# SpaceVNXDaughterBoard.net
KiCad netlist of a schematic drawn in Altium Designer
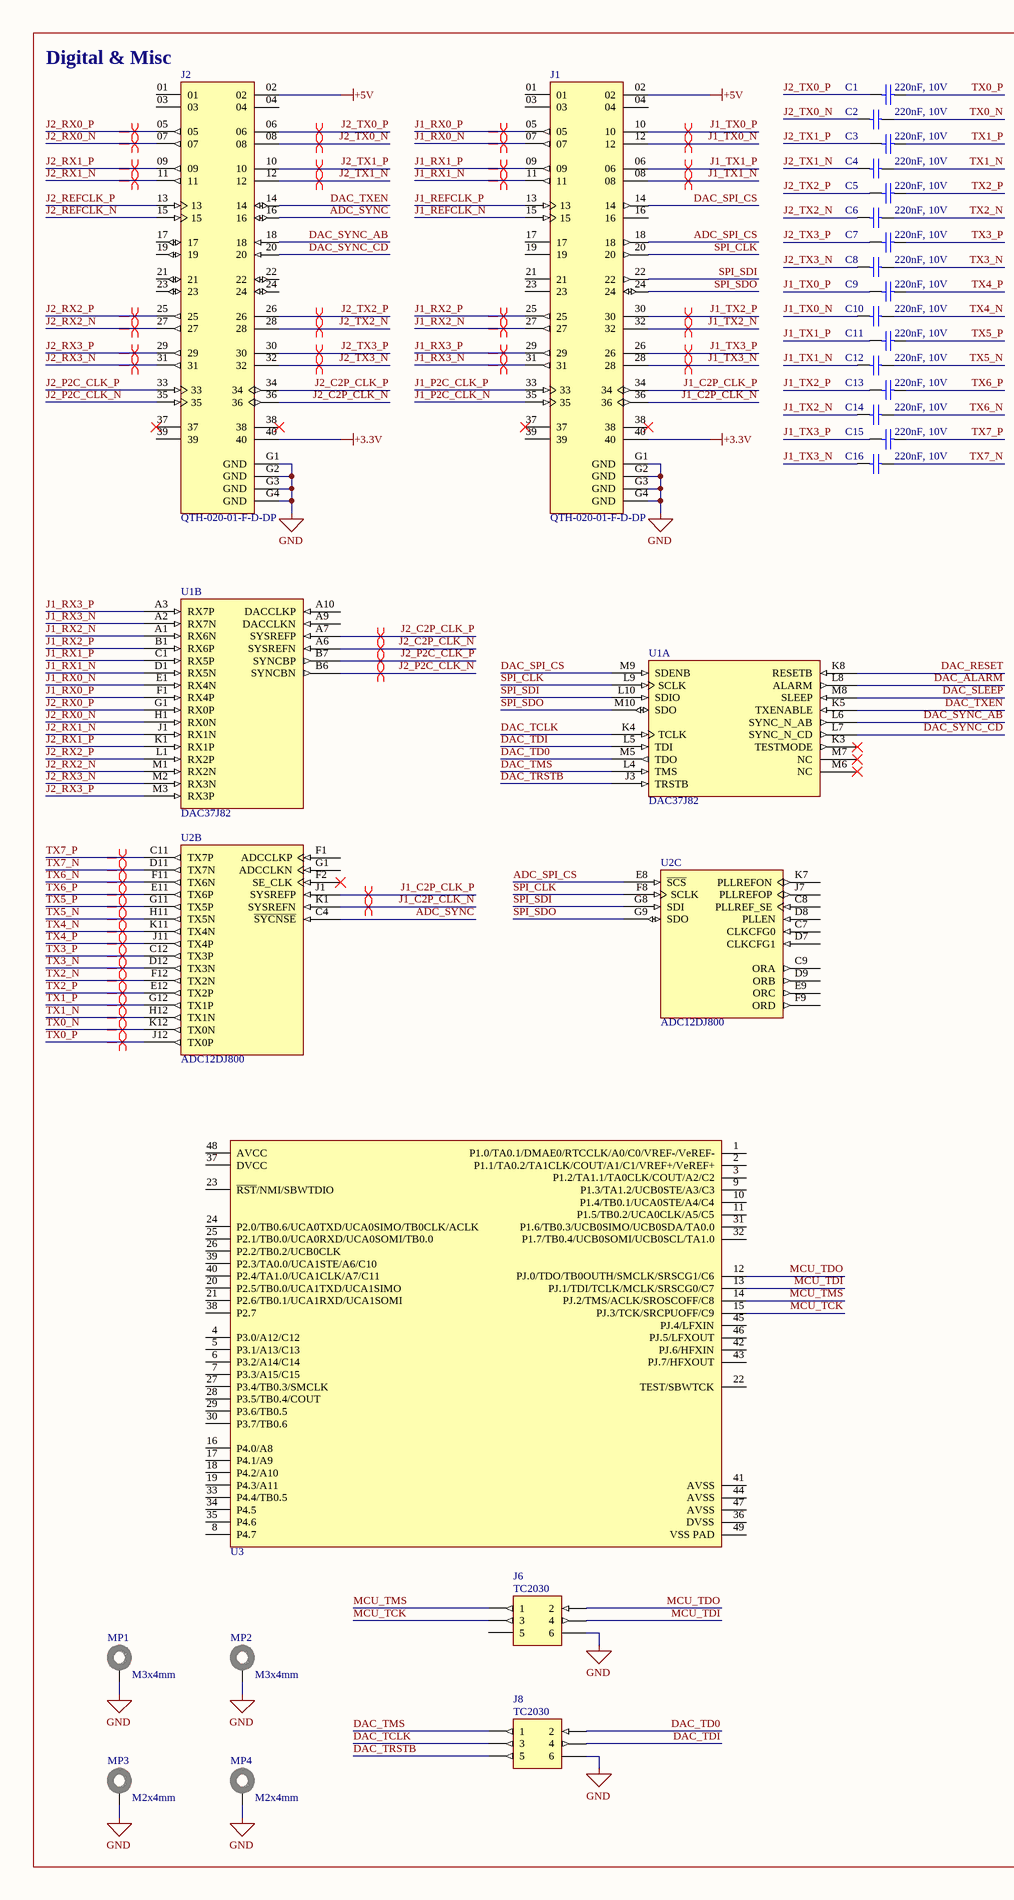
[diagram p0: SpaceVNXDaughterBoard.SchDoc, left]
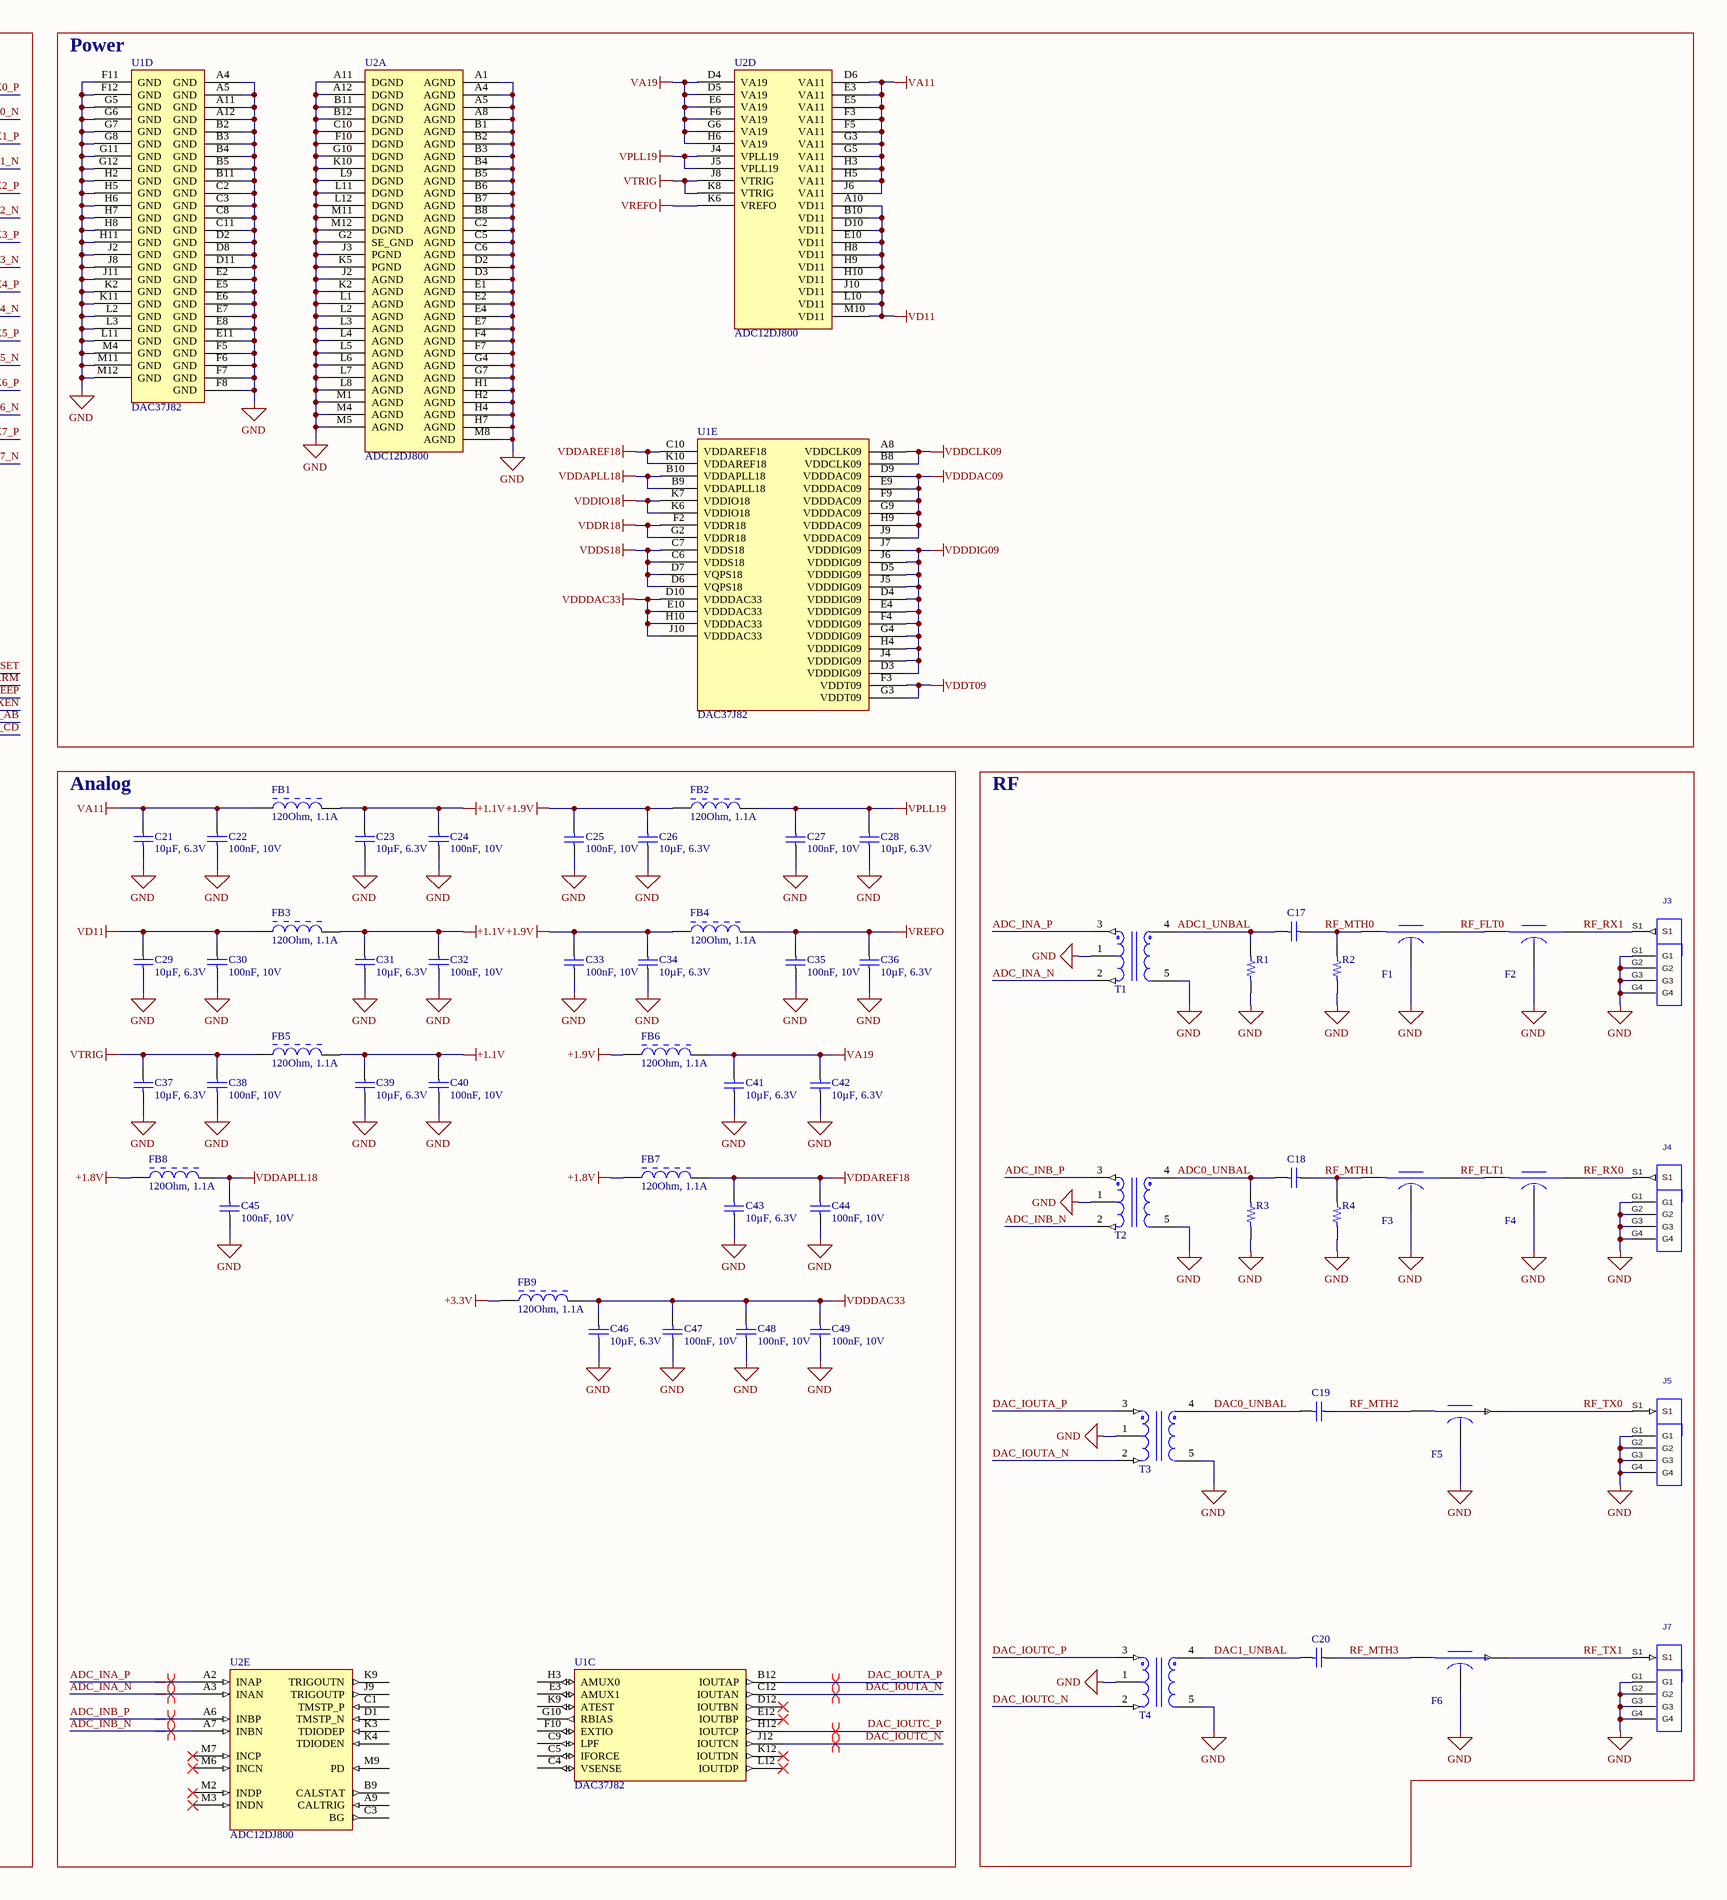
[diagram p1: SpaceVNXDaughterBoard.SchDoc, right]

(export (version "E")
  (design (tool "Eeschema 10.0.6"))
  (components
    (comp (ref "C1")
      (value "220nF, 10V")
      (footprint "WURTH_WCAP-CSGP_0402")
      (description "WCAP-CSGP Multilayer Ceramic Chip Capacitor, General Purpose, size 0402, X5R, 220nF, 10V")
      (fields
        (field (name "MANUFACTURER PART NUMBER") "885012105011")
        (field (name "MANUFACTURER") "Wurth Elektronik")
      )
      (libsource (lib "SpaceVNX") (part "885012105011"))
    )
    (comp (ref "C2")
      (value "220nF, 10V")
      (footprint "WURTH_WCAP-CSGP_0402")
      (description "WCAP-CSGP Multilayer Ceramic Chip Capacitor, General Purpose, size 0402, X5R, 220nF, 10V")
      (fields
        (field (name "MANUFACTURER PART NUMBER") "885012105011")
        (field (name "MANUFACTURER") "Wurth Elektronik")
      )
      (libsource (lib "SpaceVNX") (part "885012105011"))
    )
    (comp (ref "C3")
      (value "220nF, 10V")
      (footprint "WURTH_WCAP-CSGP_0402")
      (description "WCAP-CSGP Multilayer Ceramic Chip Capacitor, General Purpose, size 0402, X5R, 220nF, 10V")
      (fields
        (field (name "MANUFACTURER PART NUMBER") "885012105011")
        (field (name "MANUFACTURER") "Wurth Elektronik")
      )
      (libsource (lib "SpaceVNX") (part "885012105011"))
    )
    (comp (ref "C4")
      (value "220nF, 10V")
      (footprint "WURTH_WCAP-CSGP_0402")
      (description "WCAP-CSGP Multilayer Ceramic Chip Capacitor, General Purpose, size 0402, X5R, 220nF, 10V")
      (fields
        (field (name "MANUFACTURER PART NUMBER") "885012105011")
        (field (name "MANUFACTURER") "Wurth Elektronik")
      )
      (libsource (lib "SpaceVNX") (part "885012105011"))
    )
    (comp (ref "C5")
      (value "220nF, 10V")
      (footprint "WURTH_WCAP-CSGP_0402")
      (description "WCAP-CSGP Multilayer Ceramic Chip Capacitor, General Purpose, size 0402, X5R, 220nF, 10V")
      (fields
        (field (name "MANUFACTURER PART NUMBER") "885012105011")
        (field (name "MANUFACTURER") "Wurth Elektronik")
      )
      (libsource (lib "SpaceVNX") (part "885012105011"))
    )
    (comp (ref "C6")
      (value "220nF, 10V")
      (footprint "WURTH_WCAP-CSGP_0402")
      (description "WCAP-CSGP Multilayer Ceramic Chip Capacitor, General Purpose, size 0402, X5R, 220nF, 10V")
      (fields
        (field (name "MANUFACTURER PART NUMBER") "885012105011")
        (field (name "MANUFACTURER") "Wurth Elektronik")
      )
      (libsource (lib "SpaceVNX") (part "885012105011"))
    )
    (comp (ref "C7")
      (value "220nF, 10V")
      (footprint "WURTH_WCAP-CSGP_0402")
      (description "WCAP-CSGP Multilayer Ceramic Chip Capacitor, General Purpose, size 0402, X5R, 220nF, 10V")
      (fields
        (field (name "MANUFACTURER PART NUMBER") "885012105011")
        (field (name "MANUFACTURER") "Wurth Elektronik")
      )
      (libsource (lib "SpaceVNX") (part "885012105011"))
    )
    (comp (ref "C8")
      (value "220nF, 10V")
      (footprint "WURTH_WCAP-CSGP_0402")
      (description "WCAP-CSGP Multilayer Ceramic Chip Capacitor, General Purpose, size 0402, X5R, 220nF, 10V")
      (fields
        (field (name "MANUFACTURER PART NUMBER") "885012105011")
        (field (name "MANUFACTURER") "Wurth Elektronik")
      )
      (libsource (lib "SpaceVNX") (part "885012105011"))
    )
    (comp (ref "C9")
      (value "220nF, 10V")
      (footprint "WURTH_WCAP-CSGP_0402")
      (description "WCAP-CSGP Multilayer Ceramic Chip Capacitor, General Purpose, size 0402, X5R, 220nF, 10V")
      (fields
        (field (name "MANUFACTURER PART NUMBER") "885012105011")
        (field (name "MANUFACTURER") "Wurth Elektronik")
      )
      (libsource (lib "SpaceVNX") (part "885012105011"))
    )
    (comp (ref "C10")
      (value "220nF, 10V")
      (footprint "WURTH_WCAP-CSGP_0402")
      (description "WCAP-CSGP Multilayer Ceramic Chip Capacitor, General Purpose, size 0402, X5R, 220nF, 10V")
      (fields
        (field (name "MANUFACTURER PART NUMBER") "885012105011")
        (field (name "MANUFACTURER") "Wurth Elektronik")
      )
      (libsource (lib "SpaceVNX") (part "885012105011"))
    )
    (comp (ref "C11")
      (value "220nF, 10V")
      (footprint "WURTH_WCAP-CSGP_0402")
      (description "WCAP-CSGP Multilayer Ceramic Chip Capacitor, General Purpose, size 0402, X5R, 220nF, 10V")
      (fields
        (field (name "MANUFACTURER PART NUMBER") "885012105011")
        (field (name "MANUFACTURER") "Wurth Elektronik")
      )
      (libsource (lib "SpaceVNX") (part "885012105011"))
    )
    (comp (ref "C12")
      (value "220nF, 10V")
      (footprint "WURTH_WCAP-CSGP_0402")
      (description "WCAP-CSGP Multilayer Ceramic Chip Capacitor, General Purpose, size 0402, X5R, 220nF, 10V")
      (fields
        (field (name "MANUFACTURER PART NUMBER") "885012105011")
        (field (name "MANUFACTURER") "Wurth Elektronik")
      )
      (libsource (lib "SpaceVNX") (part "885012105011"))
    )
    (comp (ref "C13")
      (value "220nF, 10V")
      (footprint "WURTH_WCAP-CSGP_0402")
      (description "WCAP-CSGP Multilayer Ceramic Chip Capacitor, General Purpose, size 0402, X5R, 220nF, 10V")
      (fields
        (field (name "MANUFACTURER PART NUMBER") "885012105011")
        (field (name "MANUFACTURER") "Wurth Elektronik")
      )
      (libsource (lib "SpaceVNX") (part "885012105011"))
    )
    (comp (ref "C14")
      (value "220nF, 10V")
      (footprint "WURTH_WCAP-CSGP_0402")
      (description "WCAP-CSGP Multilayer Ceramic Chip Capacitor, General Purpose, size 0402, X5R, 220nF, 10V")
      (fields
        (field (name "MANUFACTURER PART NUMBER") "885012105011")
        (field (name "MANUFACTURER") "Wurth Elektronik")
      )
      (libsource (lib "SpaceVNX") (part "885012105011"))
    )
    (comp (ref "C15")
      (value "220nF, 10V")
      (footprint "WURTH_WCAP-CSGP_0402")
      (description "WCAP-CSGP Multilayer Ceramic Chip Capacitor, General Purpose, size 0402, X5R, 220nF, 10V")
      (fields
        (field (name "MANUFACTURER PART NUMBER") "885012105011")
        (field (name "MANUFACTURER") "Wurth Elektronik")
      )
      (libsource (lib "SpaceVNX") (part "885012105011"))
    )
    (comp (ref "C16")
      (value "220nF, 10V")
      (footprint "WURTH_WCAP-CSGP_0402")
      (description "WCAP-CSGP Multilayer Ceramic Chip Capacitor, General Purpose, size 0402, X5R, 220nF, 10V")
      (fields
        (field (name "MANUFACTURER PART NUMBER") "885012105011")
        (field (name "MANUFACTURER") "Wurth Elektronik")
      )
      (libsource (lib "SpaceVNX") (part "885012105011"))
    )
    (comp (ref "C17")
      (value "10pF, 16V")
      (footprint "WURTH_WCAP-CSGP_0402")
      (description "WCAP-CSGP Multilayer Ceramic Chip Capacitor, General Purpose, size 0402, NP0, 10pF, 16V")
      (fields
        (field (name "MANUFACTURER PART NUMBER") "885012005025")
        (field (name "MANUFACTURER") "Wurth Elektronik")
      )
      (libsource (lib "SpaceVNX") (part "885012005025"))
    )
    (comp (ref "C18")
      (value "10pF, 16V")
      (footprint "WURTH_WCAP-CSGP_0402")
      (description "WCAP-CSGP Multilayer Ceramic Chip Capacitor, General Purpose, size 0402, NP0, 10pF, 16V")
      (fields
        (field (name "MANUFACTURER PART NUMBER") "885012005025")
        (field (name "MANUFACTURER") "Wurth Elektronik")
      )
      (libsource (lib "SpaceVNX") (part "885012005025"))
    )
    (comp (ref "C19")
      (value "10pF, 16V")
      (footprint "WURTH_WCAP-CSGP_0402")
      (description "WCAP-CSGP Multilayer Ceramic Chip Capacitor, General Purpose, size 0402, NP0, 10pF, 16V")
      (fields
        (field (name "MANUFACTURER PART NUMBER") "885012005025")
        (field (name "MANUFACTURER") "Wurth Elektronik")
      )
      (libsource (lib "SpaceVNX") (part "885012005025"))
    )
    (comp (ref "C20")
      (value "10pF, 16V")
      (footprint "WURTH_WCAP-CSGP_0402")
      (description "WCAP-CSGP Multilayer Ceramic Chip Capacitor, General Purpose, size 0402, NP0, 10pF, 16V")
      (fields
        (field (name "MANUFACTURER PART NUMBER") "885012005025")
        (field (name "MANUFACTURER") "Wurth Elektronik")
      )
      (libsource (lib "SpaceVNX") (part "885012005025"))
    )
    (comp (ref "C21")
      (value "10µF, 6.3V")
      (footprint "WURTH_WCAP-CSGP_0402")
      (description "WCAP-CSGP Multilayer Ceramic Chip Capacitor, General Purpose, size 0402, X5R, 10uF, 6.3V")
      (fields
        (field (name "MANUFACTURER PART NUMBER") "885012105020")
        (field (name "MANUFACTURER") "Wurth Elektronik")
      )
      (libsource (lib "SpaceVNX") (part "885012105020"))
    )
    (comp (ref "C22")
      (value "100nF, 10V")
      (footprint "WURTH_WCAP-CSGP_0402")
      (description "WCAP-CSGP Multilayer Ceramic Chip Capacitor, General Purpose, size 0402, X7R, 100nF, 10V")
      (fields
        (field (name "MANUFACTURER PART NUMBER") "885012205018")
        (field (name "MANUFACTURER") "Wurth Elektronik")
      )
      (libsource (lib "SpaceVNX") (part "885012205018"))
    )
    (comp (ref "C23")
      (value "10µF, 6.3V")
      (footprint "WURTH_WCAP-CSGP_0402")
      (description "WCAP-CSGP Multilayer Ceramic Chip Capacitor, General Purpose, size 0402, X5R, 10uF, 6.3V")
      (fields
        (field (name "MANUFACTURER PART NUMBER") "885012105020")
        (field (name "MANUFACTURER") "Wurth Elektronik")
      )
      (libsource (lib "SpaceVNX") (part "885012105020"))
    )
    (comp (ref "C24")
      (value "100nF, 10V")
      (footprint "WURTH_WCAP-CSGP_0402")
      (description "WCAP-CSGP Multilayer Ceramic Chip Capacitor, General Purpose, size 0402, X7R, 100nF, 10V")
      (fields
        (field (name "MANUFACTURER PART NUMBER") "885012205018")
        (field (name "MANUFACTURER") "Wurth Elektronik")
      )
      (libsource (lib "SpaceVNX") (part "885012205018"))
    )
    (comp (ref "C25")
      (value "100nF, 10V")
      (footprint "WURTH_WCAP-CSGP_0402")
      (description "WCAP-CSGP Multilayer Ceramic Chip Capacitor, General Purpose, size 0402, X7R, 100nF, 10V")
      (fields
        (field (name "MANUFACTURER PART NUMBER") "885012205018")
        (field (name "MANUFACTURER") "Wurth Elektronik")
      )
      (libsource (lib "SpaceVNX") (part "885012205018"))
    )
    (comp (ref "C26")
      (value "10µF, 6.3V")
      (footprint "WURTH_WCAP-CSGP_0402")
      (description "WCAP-CSGP Multilayer Ceramic Chip Capacitor, General Purpose, size 0402, X5R, 10uF, 6.3V")
      (fields
        (field (name "MANUFACTURER PART NUMBER") "885012105020")
        (field (name "MANUFACTURER") "Wurth Elektronik")
      )
      (libsource (lib "SpaceVNX") (part "885012105020"))
    )
    (comp (ref "C27")
      (value "100nF, 10V")
      (footprint "WURTH_WCAP-CSGP_0402")
      (description "WCAP-CSGP Multilayer Ceramic Chip Capacitor, General Purpose, size 0402, X7R, 100nF, 10V")
      (fields
        (field (name "MANUFACTURER PART NUMBER") "885012205018")
        (field (name "MANUFACTURER") "Wurth Elektronik")
      )
      (libsource (lib "SpaceVNX") (part "885012205018"))
    )
    (comp (ref "C28")
      (value "10µF, 6.3V")
      (footprint "WURTH_WCAP-CSGP_0402")
      (description "WCAP-CSGP Multilayer Ceramic Chip Capacitor, General Purpose, size 0402, X5R, 10uF, 6.3V")
      (fields
        (field (name "MANUFACTURER PART NUMBER") "885012105020")
        (field (name "MANUFACTURER") "Wurth Elektronik")
      )
      (libsource (lib "SpaceVNX") (part "885012105020"))
    )
    (comp (ref "C29")
      (value "10µF, 6.3V")
      (footprint "WURTH_WCAP-CSGP_0402")
      (description "WCAP-CSGP Multilayer Ceramic Chip Capacitor, General Purpose, size 0402, X5R, 10uF, 6.3V")
      (fields
        (field (name "MANUFACTURER PART NUMBER") "885012105020")
        (field (name "MANUFACTURER") "Wurth Elektronik")
      )
      (libsource (lib "SpaceVNX") (part "885012105020"))
    )
    (comp (ref "C30")
      (value "100nF, 10V")
      (footprint "WURTH_WCAP-CSGP_0402")
      (description "WCAP-CSGP Multilayer Ceramic Chip Capacitor, General Purpose, size 0402, X7R, 100nF, 10V")
      (fields
        (field (name "MANUFACTURER PART NUMBER") "885012205018")
        (field (name "MANUFACTURER") "Wurth Elektronik")
      )
      (libsource (lib "SpaceVNX") (part "885012205018"))
    )
    (comp (ref "C31")
      (value "10µF, 6.3V")
      (footprint "WURTH_WCAP-CSGP_0402")
      (description "WCAP-CSGP Multilayer Ceramic Chip Capacitor, General Purpose, size 0402, X5R, 10uF, 6.3V")
      (fields
        (field (name "MANUFACTURER PART NUMBER") "885012105020")
        (field (name "MANUFACTURER") "Wurth Elektronik")
      )
      (libsource (lib "SpaceVNX") (part "885012105020"))
    )
    (comp (ref "C32")
      (value "100nF, 10V")
      (footprint "WURTH_WCAP-CSGP_0402")
      (description "WCAP-CSGP Multilayer Ceramic Chip Capacitor, General Purpose, size 0402, X7R, 100nF, 10V")
      (fields
        (field (name "MANUFACTURER PART NUMBER") "885012205018")
        (field (name "MANUFACTURER") "Wurth Elektronik")
      )
      (libsource (lib "SpaceVNX") (part "885012205018"))
    )
    (comp (ref "C33")
      (value "100nF, 10V")
      (footprint "WURTH_WCAP-CSGP_0402")
      (description "WCAP-CSGP Multilayer Ceramic Chip Capacitor, General Purpose, size 0402, X7R, 100nF, 10V")
      (fields
        (field (name "MANUFACTURER PART NUMBER") "885012205018")
        (field (name "MANUFACTURER") "Wurth Elektronik")
      )
      (libsource (lib "SpaceVNX") (part "885012205018"))
    )
    (comp (ref "C34")
      (value "10µF, 6.3V")
      (footprint "WURTH_WCAP-CSGP_0402")
      (description "WCAP-CSGP Multilayer Ceramic Chip Capacitor, General Purpose, size 0402, X5R, 10uF, 6.3V")
      (fields
        (field (name "MANUFACTURER PART NUMBER") "885012105020")
        (field (name "MANUFACTURER") "Wurth Elektronik")
      )
      (libsource (lib "SpaceVNX") (part "885012105020"))
    )
    (comp (ref "C35")
      (value "100nF, 10V")
      (footprint "WURTH_WCAP-CSGP_0402")
      (description "WCAP-CSGP Multilayer Ceramic Chip Capacitor, General Purpose, size 0402, X7R, 100nF, 10V")
      (fields
        (field (name "MANUFACTURER PART NUMBER") "885012205018")
        (field (name "MANUFACTURER") "Wurth Elektronik")
      )
      (libsource (lib "SpaceVNX") (part "885012205018"))
    )
    (comp (ref "C36")
      (value "10µF, 6.3V")
      (footprint "WURTH_WCAP-CSGP_0402")
      (description "WCAP-CSGP Multilayer Ceramic Chip Capacitor, General Purpose, size 0402, X5R, 10uF, 6.3V")
      (fields
        (field (name "MANUFACTURER PART NUMBER") "885012105020")
        (field (name "MANUFACTURER") "Wurth Elektronik")
      )
      (libsource (lib "SpaceVNX") (part "885012105020"))
    )
    (comp (ref "C37")
      (value "10µF, 6.3V")
      (footprint "WURTH_WCAP-CSGP_0402")
      (description "WCAP-CSGP Multilayer Ceramic Chip Capacitor, General Purpose, size 0402, X5R, 10uF, 6.3V")
      (fields
        (field (name "MANUFACTURER PART NUMBER") "885012105020")
        (field (name "MANUFACTURER") "Wurth Elektronik")
      )
      (libsource (lib "SpaceVNX") (part "885012105020"))
    )
    (comp (ref "C38")
      (value "100nF, 10V")
      (footprint "WURTH_WCAP-CSGP_0402")
      (description "WCAP-CSGP Multilayer Ceramic Chip Capacitor, General Purpose, size 0402, X7R, 100nF, 10V")
      (fields
        (field (name "MANUFACTURER PART NUMBER") "885012205018")
        (field (name "MANUFACTURER") "Wurth Elektronik")
      )
      (libsource (lib "SpaceVNX") (part "885012205018"))
    )
    (comp (ref "C39")
      (value "10µF, 6.3V")
      (footprint "WURTH_WCAP-CSGP_0402")
      (description "WCAP-CSGP Multilayer Ceramic Chip Capacitor, General Purpose, size 0402, X5R, 10uF, 6.3V")
      (fields
        (field (name "MANUFACTURER PART NUMBER") "885012105020")
        (field (name "MANUFACTURER") "Wurth Elektronik")
      )
      (libsource (lib "SpaceVNX") (part "885012105020"))
    )
    (comp (ref "C40")
      (value "100nF, 10V")
      (footprint "WURTH_WCAP-CSGP_0402")
      (description "WCAP-CSGP Multilayer Ceramic Chip Capacitor, General Purpose, size 0402, X7R, 100nF, 10V")
      (fields
        (field (name "MANUFACTURER PART NUMBER") "885012205018")
        (field (name "MANUFACTURER") "Wurth Elektronik")
      )
      (libsource (lib "SpaceVNX") (part "885012205018"))
    )
    (comp (ref "C41")
      (value "10µF, 6.3V")
      (footprint "WURTH_WCAP-CSGP_0402")
      (description "WCAP-CSGP Multilayer Ceramic Chip Capacitor, General Purpose, size 0402, X5R, 10uF, 6.3V")
      (fields
        (field (name "MANUFACTURER PART NUMBER") "885012105020")
        (field (name "MANUFACTURER") "Wurth Elektronik")
      )
      (libsource (lib "SpaceVNX") (part "885012105020"))
    )
    (comp (ref "C42")
      (value "10µF, 6.3V")
      (footprint "WURTH_WCAP-CSGP_0402")
      (description "WCAP-CSGP Multilayer Ceramic Chip Capacitor, General Purpose, size 0402, X5R, 10uF, 6.3V")
      (fields
        (field (name "MANUFACTURER PART NUMBER") "885012105020")
        (field (name "MANUFACTURER") "Wurth Elektronik")
      )
      (libsource (lib "SpaceVNX") (part "885012105020"))
    )
    (comp (ref "C43")
      (value "10µF, 6.3V")
      (footprint "WURTH_WCAP-CSGP_0402")
      (description "WCAP-CSGP Multilayer Ceramic Chip Capacitor, General Purpose, size 0402, X5R, 10uF, 6.3V")
      (fields
        (field (name "MANUFACTURER PART NUMBER") "885012105020")
        (field (name "MANUFACTURER") "Wurth Elektronik")
      )
      (libsource (lib "SpaceVNX") (part "885012105020"))
    )
    (comp (ref "C44")
      (value "100nF, 10V")
      (footprint "WURTH_WCAP-CSGP_0402")
      (description "WCAP-CSGP Multilayer Ceramic Chip Capacitor, General Purpose, size 0402, X7R, 100nF, 10V")
      (fields
        (field (name "MANUFACTURER PART NUMBER") "885012205018")
        (field (name "MANUFACTURER") "Wurth Elektronik")
      )
      (libsource (lib "SpaceVNX") (part "885012205018"))
    )
    (comp (ref "C45")
      (value "100nF, 10V")
      (footprint "WURTH_WCAP-CSGP_0402")
      (description "WCAP-CSGP Multilayer Ceramic Chip Capacitor, General Purpose, size 0402, X7R, 100nF, 10V")
      (fields
        (field (name "MANUFACTURER PART NUMBER") "885012205018")
        (field (name "MANUFACTURER") "Wurth Elektronik")
      )
      (libsource (lib "SpaceVNX") (part "885012205018"))
    )
    (comp (ref "C46")
      (value "10µF, 6.3V")
      (footprint "WURTH_WCAP-CSGP_0402")
      (description "WCAP-CSGP Multilayer Ceramic Chip Capacitor, General Purpose, size 0402, X5R, 10uF, 6.3V")
      (fields
        (field (name "MANUFACTURER PART NUMBER") "885012105020")
        (field (name "MANUFACTURER") "Wurth Elektronik")
      )
      (libsource (lib "SpaceVNX") (part "885012105020"))
    )
    (comp (ref "C47")
      (value "100nF, 10V")
      (footprint "WURTH_WCAP-CSGP_0402")
      (description "WCAP-CSGP Multilayer Ceramic Chip Capacitor, General Purpose, size 0402, X7R, 100nF, 10V")
      (fields
        (field (name "MANUFACTURER PART NUMBER") "885012205018")
        (field (name "MANUFACTURER") "Wurth Elektronik")
      )
      (libsource (lib "SpaceVNX") (part "885012205018"))
    )
    (comp (ref "C48")
      (value "100nF, 10V")
      (footprint "WURTH_WCAP-CSGP_0402")
      (description "WCAP-CSGP Multilayer Ceramic Chip Capacitor, General Purpose, size 0402, X7R, 100nF, 10V")
      (fields
        (field (name "MANUFACTURER PART NUMBER") "885012205018")
        (field (name "MANUFACTURER") "Wurth Elektronik")
      )
      (libsource (lib "SpaceVNX") (part "885012205018"))
    )
    (comp (ref "C49")
      (value "100nF, 10V")
      (footprint "WURTH_WCAP-CSGP_0402")
      (description "WCAP-CSGP Multilayer Ceramic Chip Capacitor, General Purpose, size 0402, X7R, 100nF, 10V")
      (fields
        (field (name "MANUFACTURER PART NUMBER") "885012205018")
        (field (name "MANUFACTURER") "Wurth Elektronik")
      )
      (libsource (lib "SpaceVNX") (part "885012205018"))
    )
    (comp (ref "F1")
      (value "BFTC-XXXX+")
      (footprint "Mini-Circuits_FV1206")
      (description "Band Pass RF Filter")
      (fields (field (name "MANUFACTURER") "Mini-Circuits"))
      (libsource (lib "SpaceVNX") (part "BFTC-XXXX+"))
    )
    (comp (ref "F2")
      (value "BFTC-XXXX+")
      (footprint "Mini-Circuits_FV1206")
      (description "Band Pass RF Filter")
      (fields (field (name "MANUFACTURER") "Mini-Circuits"))
      (libsource (lib "SpaceVNX") (part "BFTC-XXXX+"))
    )
    (comp (ref "F3")
      (value "BFTC-XXXX+")
      (footprint "Mini-Circuits_FV1206")
      (description "Band Pass RF Filter")
      (fields (field (name "MANUFACTURER") "Mini-Circuits"))
      (libsource (lib "SpaceVNX") (part "BFTC-XXXX+"))
    )
    (comp (ref "F4")
      (value "BFTC-XXXX+")
      (footprint "Mini-Circuits_FV1206")
      (description "Band Pass RF Filter")
      (fields (field (name "MANUFACTURER") "Mini-Circuits"))
      (libsource (lib "SpaceVNX") (part "BFTC-XXXX+"))
    )
    (comp (ref "F5")
      (value "BFTC-XXXX+")
      (footprint "Mini-Circuits_FV1206")
      (description "Band Pass RF Filter")
      (fields (field (name "MANUFACTURER") "Mini-Circuits"))
      (libsource (lib "SpaceVNX") (part "BFTC-XXXX+"))
    )
    (comp (ref "F6")
      (value "BFTC-XXXX+")
      (footprint "Mini-Circuits_FV1206")
      (description "Band Pass RF Filter")
      (fields (field (name "MANUFACTURER") "Mini-Circuits"))
      (libsource (lib "SpaceVNX") (part "BFTC-XXXX+"))
    )
    (comp (ref "FB1")
      (value "120Ohm, 1.1A")
      (footprint "WURTH-CBF_0402")
      (description "WE-CBF SMT EMI Suppression Ferrite Bead, size 0402, 120Ohm, 1.1A")
      (fields
        (field (name "MANUFACTURER PART NUMBER") "74279271")
        (field (name "MANUFACTURER") "Wurth Elektronik")
      )
      (libsource (lib "") (part "74279271_1"))
    )
    (comp (ref "FB2")
      (value "120Ohm, 1.1A")
      (footprint "WURTH-CBF_0402")
      (description "WE-CBF SMT EMI Suppression Ferrite Bead, size 0402, 120Ohm, 1.1A")
      (fields
        (field (name "MANUFACTURER PART NUMBER") "74279271")
        (field (name "MANUFACTURER") "Wurth Elektronik")
      )
      (libsource (lib "SpaceVNX") (part "74279271"))
    )
    (comp (ref "FB3")
      (value "120Ohm, 1.1A")
      (footprint "WURTH-CBF_0402")
      (description "WE-CBF SMT EMI Suppression Ferrite Bead, size 0402, 120Ohm, 1.1A")
      (fields
        (field (name "MANUFACTURER PART NUMBER") "74279271")
        (field (name "MANUFACTURER") "Wurth Elektronik")
      )
      (libsource (lib "") (part "74279271_1"))
    )
    (comp (ref "FB4")
      (value "120Ohm, 1.1A")
      (footprint "WURTH-CBF_0402")
      (description "WE-CBF SMT EMI Suppression Ferrite Bead, size 0402, 120Ohm, 1.1A")
      (fields
        (field (name "MANUFACTURER PART NUMBER") "74279271")
        (field (name "MANUFACTURER") "Wurth Elektronik")
      )
      (libsource (lib "SpaceVNX") (part "74279271"))
    )
    (comp (ref "FB5")
      (value "120Ohm, 1.1A")
      (footprint "WURTH-CBF_0402")
      (description "WE-CBF SMT EMI Suppression Ferrite Bead, size 0402, 120Ohm, 1.1A")
      (fields
        (field (name "MANUFACTURER PART NUMBER") "74279271")
        (field (name "MANUFACTURER") "Wurth Elektronik")
      )
      (libsource (lib "") (part "74279271_1"))
    )
    (comp (ref "FB6")
      (value "120Ohm, 1.1A")
      (footprint "WURTH-CBF_0402")
      (description "WE-CBF SMT EMI Suppression Ferrite Bead, size 0402, 120Ohm, 1.1A")
      (fields
        (field (name "MANUFACTURER PART NUMBER") "74279271")
        (field (name "MANUFACTURER") "Wurth Elektronik")
      )
      (libsource (lib "SpaceVNX") (part "74279271"))
    )
    (comp (ref "FB7")
      (value "120Ohm, 1.1A")
      (footprint "WURTH-CBF_0402")
      (description "WE-CBF SMT EMI Suppression Ferrite Bead, size 0402, 120Ohm, 1.1A")
      (fields
        (field (name "MANUFACTURER PART NUMBER") "74279271")
        (field (name "MANUFACTURER") "Wurth Elektronik")
      )
      (libsource (lib "SpaceVNX") (part "74279271"))
    )
    (comp (ref "FB8")
      (value "120Ohm, 1.1A")
      (footprint "WURTH-CBF_0402")
      (description "WE-CBF SMT EMI Suppression Ferrite Bead, size 0402, 120Ohm, 1.1A")
      (fields
        (field (name "MANUFACTURER PART NUMBER") "74279271")
        (field (name "MANUFACTURER") "Wurth Elektronik")
      )
      (libsource (lib "SpaceVNX") (part "74279271"))
    )
    (comp (ref "FB9")
      (value "120Ohm, 1.1A")
      (footprint "WURTH-CBF_0402")
      (description "WE-CBF SMT EMI Suppression Ferrite Bead, size 0402, 120Ohm, 1.1A")
      (fields
        (field (name "MANUFACTURER PART NUMBER") "74279271")
        (field (name "MANUFACTURER") "Wurth Elektronik")
      )
      (libsource (lib "SpaceVNX") (part "74279271"))
    )
    (comp (ref "J1")
      (value "QTH-020-01-F-D-DP")
      (footprint "SAMTEC_QTH-020-01-X-D-DP-A")
      (description "0.50 mm Q Pairs® High-Speed Ground Plane Terminal Strip, Differential Pair")
      (fields (field (name "MF") "Samtec"))
      (libsource (lib "") (part "QTH-020-01-F-D-DP_1"))
    )
    (comp (ref "J2")
      (value "QTH-020-01-F-D-DP")
      (footprint "SAMTEC_QTH-020-01-X-D-DP-A")
      (description "0.50 mm Q Pairs® High-Speed Ground Plane Terminal Strip, Differential Pair")
      (fields (field (name "MF") "Samtec"))
      (libsource (lib "SpaceVNX") (part "QTH-020-01-F-D-DP"))
    )
    (comp (ref "J3")
      (value "MMCX-J-P-X-ST-SM1")
      (footprint "MMCX-J-P-X-ST-SM1")
      (description "50 Ω MMCX up to 6 GHz")
      (fields (field (name "MANUFACTURER") "Samtec"))
      (libsource (lib "SpaceVNX") (part "MMCX-J-P-X-ST-SM1"))
    )
    (comp (ref "J4")
      (value "MMCX-J-P-X-ST-SM1")
      (footprint "MMCX-J-P-X-ST-SM1")
      (description "50 Ω MMCX up to 6 GHz")
      (fields (field (name "MANUFACTURER") "Samtec"))
      (libsource (lib "SpaceVNX") (part "MMCX-J-P-X-ST-SM1"))
    )
    (comp (ref "J5")
      (value "MMCX-J-P-X-ST-SM1")
      (footprint "MMCX-J-P-X-ST-SM1")
      (description "50 Ω MMCX up to 6 GHz")
      (fields (field (name "MANUFACTURER") "Samtec"))
      (libsource (lib "SpaceVNX") (part "MMCX-J-P-X-ST-SM1"))
    )
    (comp (ref "J6")
      (value "TC2030")
      (footprint "TC2030-DUAL")
      (description "Tag-Connect 6-pin Plug-of-Nails spring-pin cable footprint")
      (fields (field (name "MANUFACTURER") "Tag-Connect"))
      (libsource (lib "SpaceVNX") (part "TC2030"))
    )
    (comp (ref "J7")
      (value "MMCX-J-P-X-ST-SM1")
      (footprint "MMCX-J-P-X-ST-SM1")
      (description "50 Ω MMCX up to 6 GHz")
      (fields (field (name "MANUFACTURER") "Samtec"))
      (libsource (lib "SpaceVNX") (part "MMCX-J-P-X-ST-SM1"))
    )
    (comp (ref "J8")
      (value "TC2030")
      (footprint "TC2030-DUAL")
      (description "Tag-Connect 6-pin Plug-of-Nails spring-pin cable footprint")
      (fields (field (name "MANUFACTURER") "Tag-Connect"))
      (libsource (lib "SpaceVNX") (part "TC2030"))
    )
    (comp (ref "MP1")
      (value "M3x4mm")
      (footprint "90910A572")
      (description "Button Head Torx Screws 18-8 Stainless Steel, M3 x 0.5 mm Thread, 4 mm Long")
      (libsource (lib "SpaceVNXBaseBoard") (part "90910A572"))
    )
    (comp (ref "MP2")
      (value "M3x4mm")
      (footprint "90910A572")
      (description "Button Head Torx Screws 18-8 Stainless Steel, M3 x 0.5 mm Thread, 4 mm Long")
      (libsource (lib "SpaceVNXBaseBoard") (part "90910A572"))
    )
    (comp (ref "MP3")
      (value "M2x4mm")
      (footprint "90910A572")
      (description "Button Head Torx Screws 18-8 Stainless Steel, M2 x 0.4mm Thread, 4mm Long")
      (libsource (lib "SpaceVNXBaseBoard") (part "90910A920"))
    )
    (comp (ref "MP4")
      (value "M2x4mm")
      (footprint "90910A572")
      (description "Button Head Torx Screws 18-8 Stainless Steel, M2 x 0.4mm Thread, 4mm Long")
      (libsource (lib "SpaceVNXBaseBoard") (part "90910A920"))
    )
    (comp (ref "R1")
      (value "100 Ω")
      (footprint "PANASONIC_ERJ2G_0402")
      (description "General Purpose Thick Film Chip Resistors")
      (fields (field (name "MANUFACTURER") "Panasonic"))
      (libsource (lib "SpaceVNX") (part "ERJ2GEJ101X"))
    )
    (comp (ref "R2")
      (value "100 Ω")
      (footprint "PANASONIC_ERJ2G_0402")
      (description "General Purpose Thick Film Chip Resistors")
      (fields (field (name "MANUFACTURER") "Panasonic"))
      (libsource (lib "SpaceVNX") (part "ERJ2GEJ101X"))
    )
    (comp (ref "R3")
      (value "100 Ω")
      (footprint "PANASONIC_ERJ2G_0402")
      (description "General Purpose Thick Film Chip Resistors")
      (fields (field (name "MANUFACTURER") "Panasonic"))
      (libsource (lib "SpaceVNX") (part "ERJ2GEJ101X"))
    )
    (comp (ref "R4")
      (value "100 Ω")
      (footprint "PANASONIC_ERJ2G_0402")
      (description "General Purpose Thick Film Chip Resistors")
      (fields (field (name "MANUFACTURER") "Panasonic"))
      (libsource (lib "SpaceVNX") (part "ERJ2GEJ101X"))
    )
    (comp (ref "T1")
      (value "ETC1-1T-2TR")
      (footprint "MA-COM_ETC1-1T-2TR")
      (description "1:1 Flux Coupled Balun 0.1-200MHz")
      (libsource (lib "SpaceVNX") (part "ETC1-1T-2TR"))
    )
    (comp (ref "T2")
      (value "ETC1-1T-2TR")
      (footprint "MA-COM_ETC1-1T-2TR")
      (description "1:1 Flux Coupled Balun 0.1-200MHz")
      (libsource (lib "SpaceVNX") (part "ETC1-1T-2TR"))
    )
    (comp (ref "T3")
      (value "ETC1-1T-2TR")
      (footprint "MA-COM_ETC1-1T-2TR")
      (description "1:1 Flux Coupled Balun 0.1-200MHz")
      (libsource (lib "SpaceVNX") (part "ETC1-1T-2TR"))
    )
    (comp (ref "T4")
      (value "ETC1-1T-2TR")
      (footprint "MA-COM_ETC1-1T-2TR")
      (description "1:1 Flux Coupled Balun 0.1-200MHz")
      (libsource (lib "SpaceVNX") (part "ETC1-1T-2TR"))
    )
    (comp (ref "U1")
      (value "DAC37J82")
      (footprint "TEXAS_FCBGA144")
      (description "Dual-Channel, 16-Bit, 1.6/2.5 GSPS, Digital-to-Analog Converter with 12.5 Gbps JESD204B Interface.")
      (libsource (lib "") (part "DAC37J82_1"))
    )
    (comp (ref "U2")
      (value "ADC12DJ800")
      (footprint "TEXAS_FCBGA144")
      (description "Dual-Channel, 12-bit, 800-MSPS Analog-to-Digital Converter with JESD204C interface.")
      (libsource (lib "") (part "ADC12DJ800_1"))
    )
    (comp (ref "U3")
      (value "MSP430FR5969IRGZR")
      (footprint "TEXAS_VQFN48")
      (description "MSP430™ FRAM Microcontroller IC 16-Bit 16MHz 64KB (64K x 8) FRAM 48-VQFN (7x7)")
      (fields
        (field (name "MANUFACTURER") "Texas Instruments")
        (field (name "MOUSER PART NUMBER") "595-SP430FR5969IRGZR")
      )
      (libsource (lib "SpaceVNX") (part "MSP430FR5969IRGZR"))
    )
  )
  (nets
    (net (code "1") (name "+1.1V") (class "Default")
      (node (ref "C23") (pin "2") (pinfunction "2_2") (pintype "passive"))
      (node (ref "C24") (pin "2") (pinfunction "2_2") (pintype "passive"))
      (node (ref "C31") (pin "2") (pinfunction "2_2") (pintype "passive"))
      (node (ref "C32") (pin "2") (pinfunction "2_2") (pintype "passive"))
      (node (ref "C39") (pin "2") (pinfunction "2_2") (pintype "passive"))
      (node (ref "C40") (pin "2") (pinfunction "2_2") (pintype "passive"))
      (node (ref "FB1") (pin "1") (pinfunction "1_1") (pintype "passive"))
      (node (ref "FB3") (pin "1") (pinfunction "1_1") (pintype "passive"))
      (node (ref "FB5") (pin "1") (pinfunction "1_1") (pintype "passive"))
    )
    (net (code "2") (name "+1.8V") (class "Default")
      (node (ref "FB7") (pin "1") (pinfunction "1_1") (pintype "passive"))
      (node (ref "FB8") (pin "1") (pinfunction "1_1") (pintype "passive"))
    )
    (net (code "3") (name "+1.9V") (class "Default")
      (node (ref "C25") (pin "2") (pinfunction "2_2") (pintype "passive"))
      (node (ref "C26") (pin "2") (pinfunction "2_2") (pintype "passive"))
      (node (ref "C33") (pin "2") (pinfunction "2_2") (pintype "passive"))
      (node (ref "C34") (pin "2") (pinfunction "2_2") (pintype "passive"))
      (node (ref "FB2") (pin "1") (pinfunction "1_1") (pintype "passive"))
      (node (ref "FB4") (pin "1") (pinfunction "1_1") (pintype "passive"))
      (node (ref "FB6") (pin "1") (pinfunction "1_1") (pintype "passive"))
    )
    (net (code "4") (name "+3.3V") (class "Default")
      (node (ref "FB9") (pin "1") (pinfunction "1_1") (pintype "passive"))
      (node (ref "J1") (pin "40") (pinfunction "40_40") (pintype "passive"))
      (node (ref "J2") (pin "40") (pinfunction "40_40") (pintype "passive"))
    )
    (net (code "5") (name "+5V") (class "Default")
      (node (ref "J1") (pin "02") (pinfunction "02_02") (pintype "passive"))
      (node (ref "J2") (pin "02") (pinfunction "02_02") (pintype "passive"))
    )
    (net (code "6") (name "/ADC0_UNBAL") (class "Default")
      (node (ref "C18") (pin "1") (pinfunction "1_1") (pintype "passive"))
      (node (ref "R3") (pin "2") (pinfunction "2_2") (pintype "passive"))
      (node (ref "T2") (pin "4") (pinfunction "Primary_Dot_4") (pintype "passive"))
    )
    (net (code "7") (name "/ADC1_UNBAL") (class "Default")
      (node (ref "C17") (pin "1") (pinfunction "1_1") (pintype "passive"))
      (node (ref "R1") (pin "2") (pinfunction "2_2") (pintype "passive"))
      (node (ref "T1") (pin "4") (pinfunction "Primary_Dot_4") (pintype "passive"))
    )
    (net (code "8") (name "/ADC_INA_N") (class "Default")
      (node (ref "T1") (pin "2") (pinfunction "Secondary_CT_2") (pintype "output"))
      (node (ref "U2") (pin "A3") (pinfunction "INAN_A3") (pintype "input"))
    )
    (net (code "9") (name "/ADC_INA_P") (class "Default")
      (node (ref "T1") (pin "3") (pinfunction "Secondary_Dot_3") (pintype "output"))
      (node (ref "U2") (pin "A2") (pinfunction "INAP_A2") (pintype "input"))
    )
    (net (code "10") (name "/ADC_INB_N") (class "Default")
      (node (ref "T2") (pin "2") (pinfunction "Secondary_CT_2") (pintype "output"))
      (node (ref "U2") (pin "A7") (pinfunction "INBN_A7") (pintype "input"))
    )
    (net (code "11") (name "/ADC_INB_P") (class "Default")
      (node (ref "T2") (pin "3") (pinfunction "Secondary_Dot_3") (pintype "output"))
      (node (ref "U2") (pin "A6") (pinfunction "INBP_A6") (pintype "input"))
    )
    (net (code "12") (name "/ADC_SPI_CS") (class "Default")
      (node (ref "J1") (pin "18") (pinfunction "18_18") (pintype "output"))
      (node (ref "U2") (pin "E8") (pinfunction "~{SCS}_E8") (pintype "input"))
    )
    (net (code "13") (name "/ADC_SYNC") (class "Default")
      (node (ref "J2") (pin "16") (pinfunction "16_16") (pintype "bidirectional"))
      (node (ref "U2") (pin "C4") (pinfunction "~{SYCNSE}_C4") (pintype "input"))
    )
    (net (code "14") (name "/DAC0_UNBAL") (class "Default")
      (node (ref "C19") (pin "1") (pinfunction "1_1") (pintype "passive"))
      (node (ref "T3") (pin "4") (pinfunction "Primary_Dot_4") (pintype "passive"))
    )
    (net (code "15") (name "/DAC1_UNBAL") (class "Default")
      (node (ref "C20") (pin "1") (pinfunction "1_1") (pintype "passive"))
      (node (ref "T4") (pin "4") (pinfunction "Primary_Dot_4") (pintype "passive"))
    )
    (net (code "16") (name "/DAC_ALARM") (class "Default")
      (node (ref "U1") (pin "L8") (pinfunction "ALARM_L8") (pintype "output"))
    )
    (net (code "17") (name "/DAC_IOUTA_N") (class "Default")
      (node (ref "T3") (pin "2") (pinfunction "Secondary_CT_2") (pintype "output"))
      (node (ref "U1") (pin "C12") (pinfunction "IOUTAN_C12") (pintype "output"))
    )
    (net (code "18") (name "/DAC_IOUTA_P") (class "Default")
      (node (ref "T3") (pin "3") (pinfunction "Secondary_Dot_3") (pintype "output"))
      (node (ref "U1") (pin "B12") (pinfunction "IOUTAP_B12") (pintype "output"))
    )
    (net (code "19") (name "/DAC_IOUTC_N") (class "Default")
      (node (ref "T4") (pin "2") (pinfunction "Secondary_CT_2") (pintype "output"))
      (node (ref "U1") (pin "J12") (pinfunction "IOUTCN_J12") (pintype "output"))
    )
    (net (code "20") (name "/DAC_IOUTC_P") (class "Default")
      (node (ref "T4") (pin "3") (pinfunction "Secondary_Dot_3") (pintype "output"))
      (node (ref "U1") (pin "H12") (pinfunction "IOUTCP_H12") (pintype "output"))
    )
    (net (code "21") (name "/DAC_RESET") (class "Default")
      (node (ref "U1") (pin "K8") (pinfunction "RESETB_K8") (pintype "input"))
    )
    (net (code "22") (name "/DAC_SLEEP") (class "Default")
      (node (ref "U1") (pin "M8") (pinfunction "SLEEP_M8") (pintype "input"))
    )
    (net (code "23") (name "/DAC_SPI_CS") (class "Default")
      (node (ref "J1") (pin "14") (pinfunction "14_14") (pintype "output"))
      (node (ref "U1") (pin "M9") (pinfunction "SDENB_M9") (pintype "input"))
    )
    (net (code "24") (name "/DAC_SYNC_AB") (class "Default")
      (node (ref "J2") (pin "18") (pinfunction "18_18") (pintype "input"))
      (node (ref "U1") (pin "L6") (pinfunction "SYNC_N_AB_L6") (pintype "output"))
    )
    (net (code "25") (name "/DAC_SYNC_CD") (class "Default")
      (node (ref "J2") (pin "20") (pinfunction "20_20") (pintype "input"))
      (node (ref "U1") (pin "L7") (pinfunction "SYNC_N_CD_L7") (pintype "output"))
    )
    (net (code "26") (name "/DAC_TCLK") (class "Default")
      (node (ref "J8") (pin "3") (pinfunction "3_3") (pintype "output"))
      (node (ref "U1") (pin "K4") (pinfunction "TCLK_K4") (pintype "input"))
    )
    (net (code "27") (name "/DAC_TD0") (class "Default")
      (node (ref "J8") (pin "2") (pinfunction "2_2") (pintype "input"))
      (node (ref "U1") (pin "M5") (pinfunction "TDO_M5") (pintype "output"))
    )
    (net (code "28") (name "/DAC_TDI") (class "Default")
      (node (ref "J8") (pin "4") (pinfunction "4_4") (pintype "output"))
      (node (ref "U1") (pin "L5") (pinfunction "TDI_L5") (pintype "input"))
    )
    (net (code "29") (name "/DAC_TMS") (class "Default")
      (node (ref "J8") (pin "1") (pinfunction "1_1") (pintype "output"))
      (node (ref "U1") (pin "L4") (pinfunction "TMS_L4") (pintype "input"))
    )
    (net (code "30") (name "/DAC_TRSTB") (class "Default")
      (node (ref "J8") (pin "5") (pinfunction "5_5") (pintype "output"))
      (node (ref "U1") (pin "J3") (pinfunction "TRSTB_J3") (pintype "input"))
    )
    (net (code "31") (name "/DAC_TXEN") (class "Default")
      (node (ref "J2") (pin "14") (pinfunction "14_14") (pintype "bidirectional"))
      (node (ref "U1") (pin "K5") (pinfunction "TXENABLE_K5") (pintype "input"))
    )
    (net (code "32") (name "/J1_C2P_CLK_N") (class "Default")
      (node (ref "J1") (pin "36") (pinfunction "36_36") (pintype "output"))
      (node (ref "U2") (pin "K1") (pinfunction "SYSREFN_K1") (pintype "input"))
    )
    (net (code "33") (name "/J1_C2P_CLK_P") (class "Default")
      (node (ref "J1") (pin "34") (pinfunction "34_34") (pintype "output"))
      (node (ref "U2") (pin "J1") (pinfunction "SYSREFP_J1") (pintype "input"))
    )
    (net (code "34") (name "/J1_P2C_CLK_N") (class "Default")
      (node (ref "J1") (pin "35") (pinfunction "35_35") (pintype "input"))
    )
    (net (code "35") (name "/J1_P2C_CLK_P") (class "Default")
      (node (ref "J1") (pin "33") (pinfunction "33_33") (pintype "input"))
    )
    (net (code "36") (name "/J1_REFCLK_N") (class "Default")
      (node (ref "J1") (pin "15") (pinfunction "15_15") (pintype "input"))
    )
    (net (code "37") (name "/J1_REFCLK_P") (class "Default")
      (node (ref "J1") (pin "13") (pinfunction "13_13") (pintype "input"))
    )
    (net (code "38") (name "/J1_RX0_N") (class "Default")
      (node (ref "J1") (pin "07") (pinfunction "07_07") (pintype "output"))
      (node (ref "U1") (pin "E1") (pinfunction "RX4N_E1") (pintype "input"))
    )
    (net (code "39") (name "/J1_RX0_P") (class "Default")
      (node (ref "J1") (pin "05") (pinfunction "05_05") (pintype "output"))
      (node (ref "U1") (pin "F1") (pinfunction "RX4P_F1") (pintype "input"))
    )
    (net (code "40") (name "/J1_RX1_N") (class "Default")
      (node (ref "J1") (pin "11") (pinfunction "11_11") (pintype "output"))
      (node (ref "U1") (pin "D1") (pinfunction "RX5N_D1") (pintype "input"))
    )
    (net (code "41") (name "/J1_RX1_P") (class "Default")
      (node (ref "J1") (pin "09") (pinfunction "09_09") (pintype "output"))
      (node (ref "U1") (pin "C1") (pinfunction "RX5P_C1") (pintype "input"))
    )
    (net (code "42") (name "/J1_RX2_N") (class "Default")
      (node (ref "J1") (pin "27") (pinfunction "27_27") (pintype "output"))
      (node (ref "U1") (pin "A1") (pinfunction "RX6N_A1") (pintype "input"))
    )
    (net (code "43") (name "/J1_RX2_P") (class "Default")
      (node (ref "J1") (pin "25") (pinfunction "25_25") (pintype "output"))
      (node (ref "U1") (pin "B1") (pinfunction "RX6P_B1") (pintype "input"))
    )
    (net (code "44") (name "/J1_RX3_N") (class "Default")
      (node (ref "J1") (pin "31") (pinfunction "31_31") (pintype "output"))
      (node (ref "U1") (pin "A2") (pinfunction "RX7N_A2") (pintype "input"))
    )
    (net (code "45") (name "/J1_RX3_P") (class "Default")
      (node (ref "J1") (pin "29") (pinfunction "29_29") (pintype "output"))
      (node (ref "U1") (pin "A3") (pinfunction "RX7P_A3") (pintype "input"))
    )
    (net (code "46") (name "/J1_TX0_N") (class "Default")
      (node (ref "C10") (pin "1") (pinfunction "1_1") (pintype "passive"))
      (node (ref "J1") (pin "12") (pinfunction "12_12") (pintype "passive"))
    )
    (net (code "47") (name "/J1_TX0_P") (class "Default")
      (node (ref "C9") (pin "1") (pinfunction "1_1") (pintype "passive"))
      (node (ref "J1") (pin "10") (pinfunction "10_10") (pintype "passive"))
    )
    (net (code "48") (name "/J1_TX1_N") (class "Default")
      (node (ref "C12") (pin "1") (pinfunction "1_1") (pintype "passive"))
      (node (ref "J1") (pin "08") (pinfunction "08_08") (pintype "passive"))
    )
    (net (code "49") (name "/J1_TX1_P") (class "Default")
      (node (ref "C11") (pin "1") (pinfunction "1_1") (pintype "passive"))
      (node (ref "J1") (pin "06") (pinfunction "06_06") (pintype "passive"))
    )
    (net (code "50") (name "/J1_TX2_N") (class "Default")
      (node (ref "C14") (pin "1") (pinfunction "1_1") (pintype "passive"))
      (node (ref "J1") (pin "32") (pinfunction "32_32") (pintype "passive"))
    )
    (net (code "51") (name "/J1_TX2_P") (class "Default")
      (node (ref "C13") (pin "1") (pinfunction "1_1") (pintype "passive"))
      (node (ref "J1") (pin "30") (pinfunction "30_30") (pintype "passive"))
    )
    (net (code "52") (name "/J1_TX3_N") (class "Default")
      (node (ref "C16") (pin "1") (pinfunction "1_1") (pintype "passive"))
      (node (ref "J1") (pin "28") (pinfunction "28_28") (pintype "passive"))
    )
    (net (code "53") (name "/J1_TX3_P") (class "Default")
      (node (ref "C15") (pin "1") (pinfunction "1_1") (pintype "passive"))
      (node (ref "J1") (pin "26") (pinfunction "26_26") (pintype "passive"))
    )
    (net (code "54") (name "/J2_C2P_CLK_N") (class "Default")
      (node (ref "J2") (pin "36") (pinfunction "36_36") (pintype "output"))
      (node (ref "U1") (pin "A6") (pinfunction "SYSREFN_A6") (pintype "input"))
    )
    (net (code "55") (name "/J2_C2P_CLK_P") (class "Default")
      (node (ref "J2") (pin "34") (pinfunction "34_34") (pintype "output"))
      (node (ref "U1") (pin "A7") (pinfunction "SYSREFP_A7") (pintype "input"))
    )
    (net (code "56") (name "/J2_P2C_CLK_N") (class "Default")
      (node (ref "J2") (pin "35") (pinfunction "35_35") (pintype "input"))
      (node (ref "U1") (pin "B6") (pinfunction "SYNCBN_B6") (pintype "output"))
    )
    (net (code "57") (name "/J2_P2C_CLK_P") (class "Default")
      (node (ref "J2") (pin "33") (pinfunction "33_33") (pintype "input"))
      (node (ref "U1") (pin "B7") (pinfunction "SYNCBP_B7") (pintype "output"))
    )
    (net (code "58") (name "/J2_REFCLK_N") (class "Default")
      (node (ref "J2") (pin "15") (pinfunction "15_15") (pintype "input"))
    )
    (net (code "59") (name "/J2_REFCLK_P") (class "Default")
      (node (ref "J2") (pin "13") (pinfunction "13_13") (pintype "input"))
    )
    (net (code "60") (name "/J2_RX0_N") (class "Default")
      (node (ref "J2") (pin "07") (pinfunction "07_07") (pintype "output"))
      (node (ref "U1") (pin "H1") (pinfunction "RX0N_H1") (pintype "input"))
    )
    (net (code "61") (name "/J2_RX0_P") (class "Default")
      (node (ref "J2") (pin "05") (pinfunction "05_05") (pintype "output"))
      (node (ref "U1") (pin "G1") (pinfunction "RX0P_G1") (pintype "input"))
    )
    (net (code "62") (name "/J2_RX1_N") (class "Default")
      (node (ref "J2") (pin "11") (pinfunction "11_11") (pintype "output"))
      (node (ref "U1") (pin "J1") (pinfunction "RX1N_J1") (pintype "input"))
    )
    (net (code "63") (name "/J2_RX1_P") (class "Default")
      (node (ref "J2") (pin "09") (pinfunction "09_09") (pintype "output"))
      (node (ref "U1") (pin "K1") (pinfunction "RX1P_K1") (pintype "input"))
    )
    (net (code "64") (name "/J2_RX2_N") (class "Default")
      (node (ref "J2") (pin "27") (pinfunction "27_27") (pintype "output"))
      (node (ref "U1") (pin "M1") (pinfunction "RX2N_M1") (pintype "input"))
    )
    (net (code "65") (name "/J2_RX2_P") (class "Default")
      (node (ref "J2") (pin "25") (pinfunction "25_25") (pintype "output"))
      (node (ref "U1") (pin "L1") (pinfunction "RX2P_L1") (pintype "input"))
    )
    (net (code "66") (name "/J2_RX3_N") (class "Default")
      (node (ref "J2") (pin "31") (pinfunction "31_31") (pintype "output"))
      (node (ref "U1") (pin "M2") (pinfunction "RX3N_M2") (pintype "input"))
    )
    (net (code "67") (name "/J2_RX3_P") (class "Default")
      (node (ref "J2") (pin "29") (pinfunction "29_29") (pintype "output"))
      (node (ref "U1") (pin "M3") (pinfunction "RX3P_M3") (pintype "input"))
    )
    (net (code "68") (name "/J2_TX0_N") (class "Default")
      (node (ref "C2") (pin "1") (pinfunction "1_1") (pintype "passive"))
      (node (ref "J2") (pin "08") (pinfunction "08_08") (pintype "passive"))
    )
    (net (code "69") (name "/J2_TX0_P") (class "Default")
      (node (ref "C1") (pin "1") (pinfunction "1_1") (pintype "passive"))
      (node (ref "J2") (pin "06") (pinfunction "06_06") (pintype "passive"))
    )
    (net (code "70") (name "/J2_TX1_N") (class "Default")
      (node (ref "C4") (pin "1") (pinfunction "1_1") (pintype "passive"))
      (node (ref "J2") (pin "12") (pinfunction "12_12") (pintype "passive"))
    )
    (net (code "71") (name "/J2_TX1_P") (class "Default")
      (node (ref "C3") (pin "1") (pinfunction "1_1") (pintype "passive"))
      (node (ref "J2") (pin "10") (pinfunction "10_10") (pintype "passive"))
    )
    (net (code "72") (name "/J2_TX2_N") (class "Default")
      (node (ref "C6") (pin "1") (pinfunction "1_1") (pintype "passive"))
      (node (ref "J2") (pin "28") (pinfunction "28_28") (pintype "passive"))
    )
    (net (code "73") (name "/J2_TX2_P") (class "Default")
      (node (ref "C5") (pin "1") (pinfunction "1_1") (pintype "passive"))
      (node (ref "J2") (pin "26") (pinfunction "26_26") (pintype "passive"))
    )
    (net (code "74") (name "/J2_TX3_N") (class "Default")
      (node (ref "C8") (pin "1") (pinfunction "1_1") (pintype "passive"))
      (node (ref "J2") (pin "32") (pinfunction "32_32") (pintype "passive"))
    )
    (net (code "75") (name "/J2_TX3_P") (class "Default")
      (node (ref "C7") (pin "1") (pinfunction "1_1") (pintype "passive"))
      (node (ref "J2") (pin "30") (pinfunction "30_30") (pintype "passive"))
    )
    (net (code "76") (name "/MCU_TCK") (class "Default")
      (node (ref "J6") (pin "3") (pinfunction "3_3") (pintype "output"))
      (node (ref "U3") (pin "15") (pinfunction "PJ.3/TCK/SRCPUOFF/C9_15") (pintype "passive"))
    )
    (net (code "77") (name "/MCU_TDI") (class "Default")
      (node (ref "J6") (pin "4") (pinfunction "4_4") (pintype "output"))
      (node (ref "U3") (pin "13") (pinfunction "PJ.1/TDI/TCLK/MCLK/SRSCG0/C7_13") (pintype "passive"))
    )
    (net (code "78") (name "/MCU_TDO") (class "Default")
      (node (ref "J6") (pin "2") (pinfunction "2_2") (pintype "input"))
      (node (ref "U3") (pin "12") (pinfunction "PJ.0/TDO/TB0OUTH/SMCLK/SRSCG1/C6_12") (pintype "passive"))
    )
    (net (code "79") (name "/MCU_TMS") (class "Default")
      (node (ref "J6") (pin "1") (pinfunction "1_1") (pintype "output"))
      (node (ref "U3") (pin "14") (pinfunction "PJ.2/TMS/ACLK/SROSCOFF/C8_14") (pintype "passive"))
    )
    (net (code "80") (name "/RF_FLT0") (class "Default")
      (node (ref "F1") (pin "3") (pinfunction "Output_3") (pintype "output"))
      (node (ref "F2") (pin "1") (pinfunction "Input_1") (pintype "passive"))
    )
    (net (code "81") (name "/RF_FLT1") (class "Default")
      (node (ref "F3") (pin "3") (pinfunction "Output_3") (pintype "output"))
      (node (ref "F4") (pin "1") (pinfunction "Input_1") (pintype "passive"))
    )
    (net (code "82") (name "/RF_MTH0") (class "Default")
      (node (ref "C17") (pin "2") (pinfunction "2_2") (pintype "passive"))
      (node (ref "F1") (pin "1") (pinfunction "Input_1") (pintype "passive"))
      (node (ref "R2") (pin "2") (pinfunction "2_2") (pintype "passive"))
    )
    (net (code "83") (name "/RF_MTH1") (class "Default")
      (node (ref "C18") (pin "2") (pinfunction "2_2") (pintype "passive"))
      (node (ref "F3") (pin "1") (pinfunction "Input_1") (pintype "passive"))
      (node (ref "R4") (pin "2") (pinfunction "2_2") (pintype "passive"))
    )
    (net (code "84") (name "/RF_MTH2") (class "Default")
      (node (ref "C19") (pin "2") (pinfunction "2_2") (pintype "passive"))
      (node (ref "F5") (pin "1") (pinfunction "Input_1") (pintype "passive"))
    )
    (net (code "85") (name "/RF_MTH3") (class "Default")
      (node (ref "C20") (pin "2") (pinfunction "2_2") (pintype "passive"))
      (node (ref "F6") (pin "1") (pinfunction "Input_1") (pintype "passive"))
    )
    (net (code "86") (name "/RF_RX0") (class "Default")
      (node (ref "F4") (pin "3") (pinfunction "Output_3") (pintype "output"))
      (node (ref "J4") (pin "S1") (pinfunction "S1_S1") (pintype "input"))
    )
    (net (code "87") (name "/RF_RX1") (class "Default")
      (node (ref "F2") (pin "3") (pinfunction "Output_3") (pintype "output"))
      (node (ref "J3") (pin "S1") (pinfunction "S1_S1") (pintype "input"))
    )
    (net (code "88") (name "/RF_TX0") (class "Default")
      (node (ref "F5") (pin "3") (pinfunction "Output_3") (pintype "output"))
      (node (ref "J5") (pin "S1") (pinfunction "S1_S1") (pintype "input"))
    )
    (net (code "89") (name "/RF_TX1") (class "Default")
      (node (ref "F6") (pin "3") (pinfunction "Output_3") (pintype "output"))
      (node (ref "J7") (pin "S1") (pinfunction "S1_S1") (pintype "input"))
    )
    (net (code "90") (name "/SPI_CLK") (class "Default")
      (node (ref "J1") (pin "20") (pinfunction "20_20") (pintype "output"))
      (node (ref "U1") (pin "L9") (pinfunction "SCLK_L9") (pintype "input"))
      (node (ref "U2") (pin "F8") (pinfunction "SCLK_F8") (pintype "input"))
    )
    (net (code "91") (name "/SPI_SDI") (class "Default")
      (node (ref "J1") (pin "22") (pinfunction "22_22") (pintype "output"))
      (node (ref "U1") (pin "L10") (pinfunction "SDIO_L10") (pintype "bidirectional"))
      (node (ref "U2") (pin "G8") (pinfunction "SDI_G8") (pintype "input"))
    )
    (net (code "92") (name "/SPI_SDO") (class "Default")
      (node (ref "J1") (pin "24") (pinfunction "24_24") (pintype "bidirectional"))
      (node (ref "U1") (pin "M10") (pinfunction "SDO_M10") (pintype "output"))
      (node (ref "U2") (pin "G9") (pinfunction "SDO_G9") (pintype "bidirectional"))
    )
    (net (code "93") (name "/TX0_N") (class "Default")
      (node (ref "C2") (pin "2") (pinfunction "2_2") (pintype "passive"))
      (node (ref "U2") (pin "K12") (pinfunction "TX0N_K12") (pintype "output"))
    )
    (net (code "94") (name "/TX0_P") (class "Default")
      (node (ref "C1") (pin "2") (pinfunction "2_2") (pintype "passive"))
      (node (ref "U2") (pin "J12") (pinfunction "TX0P_J12") (pintype "output"))
    )
    (net (code "95") (name "/TX1_N") (class "Default")
      (node (ref "C4") (pin "2") (pinfunction "2_2") (pintype "passive"))
      (node (ref "U2") (pin "H12") (pinfunction "TX1N_H12") (pintype "output"))
    )
    (net (code "96") (name "/TX1_P") (class "Default")
      (node (ref "C3") (pin "2") (pinfunction "2_2") (pintype "passive"))
      (node (ref "U2") (pin "G12") (pinfunction "TX1P_G12") (pintype "output"))
    )
    (net (code "97") (name "/TX2_N") (class "Default")
      (node (ref "C6") (pin "2") (pinfunction "2_2") (pintype "passive"))
      (node (ref "U2") (pin "F12") (pinfunction "TX2N_F12") (pintype "output"))
    )
    (net (code "98") (name "/TX2_P") (class "Default")
      (node (ref "C5") (pin "2") (pinfunction "2_2") (pintype "passive"))
      (node (ref "U2") (pin "E12") (pinfunction "TX2P_E12") (pintype "output"))
    )
    (net (code "99") (name "/TX3_N") (class "Default")
      (node (ref "C8") (pin "2") (pinfunction "2_2") (pintype "passive"))
      (node (ref "U2") (pin "D12") (pinfunction "TX3N_D12") (pintype "output"))
    )
    (net (code "100") (name "/TX3_P") (class "Default")
      (node (ref "C7") (pin "2") (pinfunction "2_2") (pintype "passive"))
      (node (ref "U2") (pin "C12") (pinfunction "TX3P_C12") (pintype "output"))
    )
    (net (code "101") (name "/TX4_N") (class "Default")
      (node (ref "C10") (pin "2") (pinfunction "2_2") (pintype "passive"))
      (node (ref "U2") (pin "K11") (pinfunction "TX4N_K11") (pintype "output"))
    )
    (net (code "102") (name "/TX4_P") (class "Default")
      (node (ref "C9") (pin "2") (pinfunction "2_2") (pintype "passive"))
      (node (ref "U2") (pin "J11") (pinfunction "TX4P_J11") (pintype "output"))
    )
    (net (code "103") (name "/TX5_N") (class "Default")
      (node (ref "C12") (pin "2") (pinfunction "2_2") (pintype "passive"))
      (node (ref "U2") (pin "H11") (pinfunction "TX5N_H11") (pintype "output"))
    )
    (net (code "104") (name "/TX5_P") (class "Default")
      (node (ref "C11") (pin "2") (pinfunction "2_2") (pintype "passive"))
      (node (ref "U2") (pin "G11") (pinfunction "TX5P_G11") (pintype "output"))
    )
    (net (code "105") (name "/TX6_N") (class "Default")
      (node (ref "C14") (pin "2") (pinfunction "2_2") (pintype "passive"))
      (node (ref "U2") (pin "F11") (pinfunction "TX6N_F11") (pintype "output"))
    )
    (net (code "106") (name "/TX6_P") (class "Default")
      (node (ref "C13") (pin "2") (pinfunction "2_2") (pintype "passive"))
      (node (ref "U2") (pin "E11") (pinfunction "TX6P_E11") (pintype "output"))
    )
    (net (code "107") (name "/TX7_N") (class "Default")
      (node (ref "C16") (pin "2") (pinfunction "2_2") (pintype "passive"))
      (node (ref "U2") (pin "D11") (pinfunction "TX7N_D11") (pintype "output"))
    )
    (net (code "108") (name "/TX7_P") (class "Default")
      (node (ref "C15") (pin "2") (pinfunction "2_2") (pintype "passive"))
      (node (ref "U2") (pin "C11") (pinfunction "TX7P_C11") (pintype "output"))
    )
    (net (code "109") (name "GND") (class "Default")
      (node (ref "C21") (pin "1") (pinfunction "1_1") (pintype "passive"))
      (node (ref "C22") (pin "1") (pinfunction "1_1") (pintype "passive"))
      (node (ref "C23") (pin "1") (pinfunction "1_1") (pintype "passive"))
      (node (ref "C24") (pin "1") (pinfunction "1_1") (pintype "passive"))
      (node (ref "C25") (pin "1") (pinfunction "1_1") (pintype "passive"))
      (node (ref "C26") (pin "1") (pinfunction "1_1") (pintype "passive"))
      (node (ref "C27") (pin "1") (pinfunction "1_1") (pintype "passive"))
      (node (ref "C28") (pin "1") (pinfunction "1_1") (pintype "passive"))
      (node (ref "C29") (pin "1") (pinfunction "1_1") (pintype "passive"))
      (node (ref "C30") (pin "1") (pinfunction "1_1") (pintype "passive"))
      (node (ref "C31") (pin "1") (pinfunction "1_1") (pintype "passive"))
      (node (ref "C32") (pin "1") (pinfunction "1_1") (pintype "passive"))
      (node (ref "C33") (pin "1") (pinfunction "1_1") (pintype "passive"))
      (node (ref "C34") (pin "1") (pinfunction "1_1") (pintype "passive"))
      (node (ref "C35") (pin "1") (pinfunction "1_1") (pintype "passive"))
      (node (ref "C36") (pin "1") (pinfunction "1_1") (pintype "passive"))
      (node (ref "C37") (pin "1") (pinfunction "1_1") (pintype "passive"))
      (node (ref "C38") (pin "1") (pinfunction "1_1") (pintype "passive"))
      (node (ref "C39") (pin "1") (pinfunction "1_1") (pintype "passive"))
      (node (ref "C40") (pin "1") (pinfunction "1_1") (pintype "passive"))
      (node (ref "C41") (pin "1") (pinfunction "1_1") (pintype "passive"))
      (node (ref "C42") (pin "1") (pinfunction "1_1") (pintype "passive"))
      (node (ref "C43") (pin "1") (pinfunction "1_1") (pintype "passive"))
      (node (ref "C44") (pin "1") (pinfunction "1_1") (pintype "passive"))
      (node (ref "C45") (pin "1") (pinfunction "1_1") (pintype "passive"))
      (node (ref "C46") (pin "1") (pinfunction "1_1") (pintype "passive"))
      (node (ref "C47") (pin "1") (pinfunction "1_1") (pintype "passive"))
      (node (ref "C48") (pin "1") (pinfunction "1_1") (pintype "passive"))
      (node (ref "C49") (pin "1") (pinfunction "1_1") (pintype "passive"))
      (node (ref "F1") (pin "2") (pinfunction "GND_2") (pintype "passive"))
      (node (ref "F2") (pin "2") (pinfunction "GND_2") (pintype "passive"))
      (node (ref "F3") (pin "2") (pinfunction "GND_2") (pintype "passive"))
      (node (ref "F4") (pin "2") (pinfunction "GND_2") (pintype "passive"))
      (node (ref "F5") (pin "2") (pinfunction "GND_2") (pintype "passive"))
      (node (ref "F6") (pin "2") (pinfunction "GND_2") (pintype "passive"))
      (node (ref "J1") (pin "G1") (pinfunction "GND_G1") (pintype "power_in"))
      (node (ref "J1") (pin "G2") (pinfunction "GND_G2") (pintype "power_in"))
      (node (ref "J1") (pin "G3") (pinfunction "GND_G3") (pintype "power_in"))
      (node (ref "J1") (pin "G4") (pinfunction "GND_G4") (pintype "power_in"))
      (node (ref "J2") (pin "G1") (pinfunction "GND_G1") (pintype "power_in"))
      (node (ref "J2") (pin "G2") (pinfunction "GND_G2") (pintype "power_in"))
      (node (ref "J2") (pin "G3") (pinfunction "GND_G3") (pintype "power_in"))
      (node (ref "J2") (pin "G4") (pinfunction "GND_G4") (pintype "power_in"))
      (node (ref "J3") (pin "G1") (pinfunction "G1_G1") (pintype "passive"))
      (node (ref "J3") (pin "G2") (pinfunction "G2_G2") (pintype "passive"))
      (node (ref "J3") (pin "G3") (pinfunction "G3_G3") (pintype "passive"))
      (node (ref "J3") (pin "G4") (pinfunction "G4_G4") (pintype "passive"))
      (node (ref "J4") (pin "G1") (pinfunction "G1_G1") (pintype "passive"))
      (node (ref "J4") (pin "G2") (pinfunction "G2_G2") (pintype "passive"))
      (node (ref "J4") (pin "G3") (pinfunction "G3_G3") (pintype "passive"))
      (node (ref "J4") (pin "G4") (pinfunction "G4_G4") (pintype "passive"))
      (node (ref "J5") (pin "G1") (pinfunction "G1_G1") (pintype "passive"))
      (node (ref "J5") (pin "G2") (pinfunction "G2_G2") (pintype "passive"))
      (node (ref "J5") (pin "G3") (pinfunction "G3_G3") (pintype "passive"))
      (node (ref "J5") (pin "G4") (pinfunction "G4_G4") (pintype "passive"))
      (node (ref "J6") (pin "6") (pinfunction "6_6") (pintype "passive"))
      (node (ref "J7") (pin "G1") (pinfunction "G1_G1") (pintype "passive"))
      (node (ref "J7") (pin "G2") (pinfunction "G2_G2") (pintype "passive"))
      (node (ref "J7") (pin "G3") (pinfunction "G3_G3") (pintype "passive"))
      (node (ref "J7") (pin "G4") (pinfunction "G4_G4") (pintype "passive"))
      (node (ref "J8") (pin "6") (pinfunction "6_6") (pintype "passive"))
      (node (ref "MP1") (pin "1") (pinfunction "1_1") (pintype "passive"))
      (node (ref "MP2") (pin "1") (pinfunction "1_1") (pintype "passive"))
      (node (ref "MP3") (pin "1") (pinfunction "1_1") (pintype "passive"))
      (node (ref "MP4") (pin "1") (pinfunction "1_1") (pintype "passive"))
      (node (ref "R1") (pin "1") (pinfunction "1_1") (pintype "passive"))
      (node (ref "R2") (pin "1") (pinfunction "1_1") (pintype "passive"))
      (node (ref "R3") (pin "1") (pinfunction "1_1") (pintype "passive"))
      (node (ref "R4") (pin "1") (pinfunction "1_1") (pintype "passive"))
      (node (ref "T1") (pin "1") (pinfunction "Secondary_1") (pintype "passive"))
      (node (ref "T1") (pin "5") (pinfunction "Primary_5") (pintype "passive"))
      (node (ref "T2") (pin "1") (pinfunction "Secondary_1") (pintype "passive"))
      (node (ref "T2") (pin "5") (pinfunction "Primary_5") (pintype "passive"))
      (node (ref "T3") (pin "1") (pinfunction "Secondary_1") (pintype "passive"))
      (node (ref "T3") (pin "5") (pinfunction "Primary_5") (pintype "passive"))
      (node (ref "T4") (pin "1") (pinfunction "Secondary_1") (pintype "passive"))
      (node (ref "T4") (pin "5") (pinfunction "Primary_5") (pintype "passive"))
      (node (ref "U1") (pin "A11") (pinfunction "GND_A11") (pintype "passive"))
      (node (ref "U1") (pin "A12") (pinfunction "GND_A12") (pintype "passive"))
      (node (ref "U1") (pin "A4") (pinfunction "GND_A4") (pintype "passive"))
      (node (ref "U1") (pin "A5") (pinfunction "GND_A5") (pintype "passive"))
      (node (ref "U1") (pin "B11") (pinfunction "GND_B11") (pintype "passive"))
      (node (ref "U1") (pin "B2") (pinfunction "GND_B2") (pintype "passive"))
      (node (ref "U1") (pin "B3") (pinfunction "GND_B3") (pintype "passive"))
      (node (ref "U1") (pin "B4") (pinfunction "GND_B4") (pintype "passive"))
      (node (ref "U1") (pin "B5") (pinfunction "GND_B5") (pintype "passive"))
      (node (ref "U1") (pin "C11") (pinfunction "GND_C11") (pintype "passive"))
      (node (ref "U1") (pin "C2") (pinfunction "GND_C2") (pintype "passive"))
      (node (ref "U1") (pin "C3") (pinfunction "GND_C3") (pintype "passive"))
      (node (ref "U1") (pin "C8") (pinfunction "GND_C8") (pintype "passive"))
      (node (ref "U1") (pin "D11") (pinfunction "GND_D11") (pintype "passive"))
      (node (ref "U1") (pin "D2") (pinfunction "GND_D2") (pintype "passive"))
      (node (ref "U1") (pin "D8") (pinfunction "GND_D8") (pintype "passive"))
      (node (ref "U1") (pin "E11") (pinfunction "GND_E11") (pintype "passive"))
      (node (ref "U1") (pin "E2") (pinfunction "GND_E2") (pintype "passive"))
      (node (ref "U1") (pin "E5") (pinfunction "GND_E5") (pintype "passive"))
      (node (ref "U1") (pin "E6") (pinfunction "GND_E6") (pintype "passive"))
      (node (ref "U1") (pin "E7") (pinfunction "GND_E7") (pintype "passive"))
      (node (ref "U1") (pin "E8") (pinfunction "GND_E8") (pintype "passive"))
      (node (ref "U1") (pin "F11") (pinfunction "GND_F11") (pintype "passive"))
      (node (ref "U1") (pin "F12") (pinfunction "GND_F12") (pintype "passive"))
      (node (ref "U1") (pin "F5") (pinfunction "GND_F5") (pintype "passive"))
      (node (ref "U1") (pin "F6") (pinfunction "GND_F6") (pintype "passive"))
      (node (ref "U1") (pin "F7") (pinfunction "GND_F7") (pintype "passive"))
      (node (ref "U1") (pin "F8") (pinfunction "GND_F8") (pintype "passive"))
      (node (ref "U1") (pin "G11") (pinfunction "GND_G11") (pintype "passive"))
      (node (ref "U1") (pin "G12") (pinfunction "GND_G12") (pintype "passive"))
      (node (ref "U1") (pin "G5") (pinfunction "GND_G5") (pintype "passive"))
      (node (ref "U1") (pin "G6") (pinfunction "GND_G6") (pintype "passive"))
      (node (ref "U1") (pin "G7") (pinfunction "GND_G7") (pintype "passive"))
      (node (ref "U1") (pin "G8") (pinfunction "GND_G8") (pintype "passive"))
      (node (ref "U1") (pin "H11") (pinfunction "GND_H11") (pintype "passive"))
      (node (ref "U1") (pin "H2") (pinfunction "GND_H2") (pintype "passive"))
      (node (ref "U1") (pin "H5") (pinfunction "GND_H5") (pintype "passive"))
      (node (ref "U1") (pin "H6") (pinfunction "GND_H6") (pintype "passive"))
      (node (ref "U1") (pin "H7") (pinfunction "GND_H7") (pintype "passive"))
      (node (ref "U1") (pin "H8") (pinfunction "GND_H8") (pintype "passive"))
      (node (ref "U1") (pin "J11") (pinfunction "GND_J11") (pintype "passive"))
      (node (ref "U1") (pin "J2") (pinfunction "GND_J2") (pintype "passive"))
      (node (ref "U1") (pin "J8") (pinfunction "GND_J8") (pintype "passive"))
      (node (ref "U1") (pin "K11") (pinfunction "GND_K11") (pintype "passive"))
      (node (ref "U1") (pin "K2") (pinfunction "GND_K2") (pintype "passive"))
      (node (ref "U1") (pin "L11") (pinfunction "GND_L11") (pintype "passive"))
      (node (ref "U1") (pin "L2") (pinfunction "GND_L2") (pintype "passive"))
      (node (ref "U1") (pin "L3") (pinfunction "GND_L3") (pintype "passive"))
      (node (ref "U1") (pin "M11") (pinfunction "GND_M11") (pintype "passive"))
      (node (ref "U1") (pin "M12") (pinfunction "GND_M12") (pintype "passive"))
      (node (ref "U1") (pin "M4") (pinfunction "GND_M4") (pintype "passive"))
      (node (ref "U2") (pin "A1") (pinfunction "AGND_A1") (pintype "passive"))
      (node (ref "U2") (pin "A11") (pinfunction "DGND_A11") (pintype "passive"))
      (node (ref "U2") (pin "A12") (pinfunction "DGND_A12") (pintype "passive"))
      (node (ref "U2") (pin "A4") (pinfunction "AGND_A4") (pintype "passive"))
      (node (ref "U2") (pin "A5") (pinfunction "AGND_A5") (pintype "passive"))
      (node (ref "U2") (pin "A8") (pinfunction "AGND_A8") (pintype "passive"))
      (node (ref "U2") (pin "B1") (pinfunction "AGND_B1") (pintype "passive"))
      (node (ref "U2") (pin "B11") (pinfunction "DGND_B11") (pintype "passive"))
      (node (ref "U2") (pin "B12") (pinfunction "DGND_B12") (pintype "passive"))
      (node (ref "U2") (pin "B2") (pinfunction "AGND_B2") (pintype "passive"))
      (node (ref "U2") (pin "B3") (pinfunction "AGND_B3") (pintype "passive"))
      (node (ref "U2") (pin "B4") (pinfunction "AGND_B4") (pintype "passive"))
      (node (ref "U2") (pin "B5") (pinfunction "AGND_B5") (pintype "passive"))
      (node (ref "U2") (pin "B6") (pinfunction "AGND_B6") (pintype "passive"))
      (node (ref "U2") (pin "B7") (pinfunction "AGND_B7") (pintype "passive"))
      (node (ref "U2") (pin "B8") (pinfunction "AGND_B8") (pintype "passive"))
      (node (ref "U2") (pin "C10") (pinfunction "DGND_C10") (pintype "passive"))
      (node (ref "U2") (pin "C2") (pinfunction "AGND_C2") (pintype "passive"))
      (node (ref "U2") (pin "C5") (pinfunction "AGND_C5") (pintype "passive"))
      (node (ref "U2") (pin "C6") (pinfunction "AGND_C6") (pintype "passive"))
      (node (ref "U2") (pin "D2") (pinfunction "AGND_D2") (pintype "passive"))
      (node (ref "U2") (pin "D3") (pinfunction "AGND_D3") (pintype "passive"))
      (node (ref "U2") (pin "E1") (pinfunction "AGND_E1") (pintype "passive"))
      (node (ref "U2") (pin "E2") (pinfunction "AGND_E2") (pintype "passive"))
      (node (ref "U2") (pin "E4") (pinfunction "AGND_E4") (pintype "passive"))
      (node (ref "U2") (pin "E7") (pinfunction "AGND_E7") (pintype "passive"))
      (node (ref "U2") (pin "F10") (pinfunction "DGND_F10") (pintype "passive"))
      (node (ref "U2") (pin "F4") (pinfunction "AGND_F4") (pintype "passive"))
      (node (ref "U2") (pin "F7") (pinfunction "AGND_F7") (pintype "passive"))
      (node (ref "U2") (pin "G10") (pinfunction "DGND_G10") (pintype "passive"))
      (node (ref "U2") (pin "G2") (pinfunction "SE_GND_G2") (pintype "passive"))
      (node (ref "U2") (pin "G4") (pinfunction "AGND_G4") (pintype "passive"))
      (node (ref "U2") (pin "G7") (pinfunction "AGND_G7") (pintype "passive"))
      (node (ref "U2") (pin "H1") (pinfunction "AGND_H1") (pintype "passive"))
      (node (ref "U2") (pin "H2") (pinfunction "AGND_H2") (pintype "passive"))
      (node (ref "U2") (pin "H4") (pinfunction "AGND_H4") (pintype "passive"))
      (node (ref "U2") (pin "H7") (pinfunction "AGND_H7") (pintype "passive"))
      (node (ref "U2") (pin "J2") (pinfunction "AGND_J2") (pintype "passive"))
      (node (ref "U2") (pin "J3") (pinfunction "PGND_J3") (pintype "passive"))
      (node (ref "U2") (pin "K10") (pinfunction "DGND_K10") (pintype "passive"))
      (node (ref "U2") (pin "K2") (pinfunction "AGND_K2") (pintype "passive"))
      (node (ref "U2") (pin "K5") (pinfunction "PGND_K5") (pintype "passive"))
      (node (ref "U2") (pin "L1") (pinfunction "AGND_L1") (pintype "passive"))
      (node (ref "U2") (pin "L11") (pinfunction "DGND_L11") (pintype "passive"))
      (node (ref "U2") (pin "L12") (pinfunction "DGND_L12") (pintype "passive"))
      (node (ref "U2") (pin "L2") (pinfunction "AGND_L2") (pintype "passive"))
      (node (ref "U2") (pin "L3") (pinfunction "AGND_L3") (pintype "passive"))
      (node (ref "U2") (pin "L4") (pinfunction "AGND_L4") (pintype "passive"))
      (node (ref "U2") (pin "L5") (pinfunction "AGND_L5") (pintype "passive"))
      (node (ref "U2") (pin "L6") (pinfunction "AGND_L6") (pintype "passive"))
      (node (ref "U2") (pin "L7") (pinfunction "AGND_L7") (pintype "passive"))
      (node (ref "U2") (pin "L8") (pinfunction "AGND_L8") (pintype "passive"))
      (node (ref "U2") (pin "L9") (pinfunction "DGND_L9") (pintype "passive"))
      (node (ref "U2") (pin "M1") (pinfunction "AGND_M1") (pintype "passive"))
      (node (ref "U2") (pin "M11") (pinfunction "DGND_M11") (pintype "passive"))
      (node (ref "U2") (pin "M12") (pinfunction "DGND_M12") (pintype "passive"))
      (node (ref "U2") (pin "M4") (pinfunction "AGND_M4") (pintype "passive"))
      (node (ref "U2") (pin "M5") (pinfunction "AGND_M5") (pintype "passive"))
      (node (ref "U2") (pin "M8") (pinfunction "AGND_M8") (pintype "passive"))
    )
    (net (code "110") (name "VA11") (class "Default")
      (node (ref "C21") (pin "2") (pinfunction "2_2") (pintype "passive"))
      (node (ref "C22") (pin "2") (pinfunction "2_2") (pintype "passive"))
      (node (ref "FB1") (pin "2") (pinfunction "2_2") (pintype "passive"))
      (node (ref "U2") (pin "D6") (pinfunction "VA11_D6") (pintype "passive"))
      (node (ref "U2") (pin "E3") (pinfunction "VA11_E3") (pintype "passive"))
      (node (ref "U2") (pin "E5") (pinfunction "VA11_E5") (pintype "passive"))
      (node (ref "U2") (pin "F3") (pinfunction "VA11_F3") (pintype "passive"))
      (node (ref "U2") (pin "F5") (pinfunction "VA11_F5") (pintype "passive"))
      (node (ref "U2") (pin "G3") (pinfunction "VA11_G3") (pintype "passive"))
      (node (ref "U2") (pin "G5") (pinfunction "VA11_G5") (pintype "passive"))
      (node (ref "U2") (pin "H3") (pinfunction "VA11_H3") (pintype "passive"))
      (node (ref "U2") (pin "H5") (pinfunction "VA11_H5") (pintype "passive"))
      (node (ref "U2") (pin "J6") (pinfunction "VA11_J6") (pintype "passive"))
    )
    (net (code "111") (name "VA19") (class "Default")
      (node (ref "C41") (pin "2") (pinfunction "2_2") (pintype "passive"))
      (node (ref "C42") (pin "2") (pinfunction "2_2") (pintype "passive"))
      (node (ref "FB6") (pin "2") (pinfunction "2_2") (pintype "passive"))
      (node (ref "U2") (pin "D4") (pinfunction "VA19_D4") (pintype "passive"))
      (node (ref "U2") (pin "D5") (pinfunction "VA19_D5") (pintype "passive"))
      (node (ref "U2") (pin "E6") (pinfunction "VA19_E6") (pintype "passive"))
      (node (ref "U2") (pin "F6") (pinfunction "VA19_F6") (pintype "passive"))
      (node (ref "U2") (pin "G6") (pinfunction "VA19_G6") (pintype "passive"))
      (node (ref "U2") (pin "H6") (pinfunction "VA19_H6") (pintype "passive"))
    )
    (net (code "112") (name "VD11") (class "Default")
      (node (ref "C29") (pin "2") (pinfunction "2_2") (pintype "passive"))
      (node (ref "C30") (pin "2") (pinfunction "2_2") (pintype "passive"))
      (node (ref "FB3") (pin "2") (pinfunction "2_2") (pintype "passive"))
      (node (ref "U2") (pin "A10") (pinfunction "VD11_A10") (pintype "passive"))
      (node (ref "U2") (pin "B10") (pinfunction "VD11_B10") (pintype "passive"))
      (node (ref "U2") (pin "D10") (pinfunction "VD11_D10") (pintype "passive"))
      (node (ref "U2") (pin "E10") (pinfunction "VD11_E10") (pintype "passive"))
      (node (ref "U2") (pin "H10") (pinfunction "VD11_H10") (pintype "passive"))
      (node (ref "U2") (pin "H8") (pinfunction "VD11_H8") (pintype "passive"))
      (node (ref "U2") (pin "H9") (pinfunction "VD11_H9") (pintype "passive"))
      (node (ref "U2") (pin "J10") (pinfunction "VD11_J10") (pintype "passive"))
      (node (ref "U2") (pin "L10") (pinfunction "VD11_L10") (pintype "passive"))
      (node (ref "U2") (pin "M10") (pinfunction "VD11_M10") (pintype "passive"))
    )
    (net (code "113") (name "VDDAPLL18") (class "Default")
      (node (ref "C45") (pin "2") (pinfunction "2_2") (pintype "passive"))
      (node (ref "FB8") (pin "2") (pinfunction "2_2") (pintype "passive"))
      (node (ref "U1") (pin "B10") (pinfunction "VDDAPLL18_B10") (pintype "passive"))
      (node (ref "U1") (pin "B9") (pinfunction "VDDAPLL18_B9") (pintype "passive"))
    )
    (net (code "114") (name "VDDAREF18") (class "Default")
      (node (ref "C43") (pin "2") (pinfunction "2_2") (pintype "passive"))
      (node (ref "C44") (pin "2") (pinfunction "2_2") (pintype "passive"))
      (node (ref "FB7") (pin "2") (pinfunction "2_2") (pintype "passive"))
      (node (ref "U1") (pin "C10") (pinfunction "VDDAREF18_C10") (pintype "passive"))
      (node (ref "U1") (pin "K10") (pinfunction "VDDAREF18_K10") (pintype "passive"))
    )
    (net (code "115") (name "VDDCLK09") (class "Default")
      (node (ref "U1") (pin "A8") (pinfunction "VDDCLK09_A8") (pintype "passive"))
      (node (ref "U1") (pin "B8") (pinfunction "VDDCLK09_B8") (pintype "passive"))
    )
    (net (code "116") (name "VDDDAC09") (class "Default")
      (node (ref "U1") (pin "D9") (pinfunction "VDDDAC09_D9") (pintype "passive"))
      (node (ref "U1") (pin "E9") (pinfunction "VDDDAC09_E9") (pintype "passive"))
      (node (ref "U1") (pin "F9") (pinfunction "VDDDAC09_F9") (pintype "passive"))
      (node (ref "U1") (pin "G9") (pinfunction "VDDDAC09_G9") (pintype "passive"))
      (node (ref "U1") (pin "H9") (pinfunction "VDDDAC09_H9") (pintype "passive"))
      (node (ref "U1") (pin "J9") (pinfunction "VDDDAC09_J9") (pintype "passive"))
    )
    (net (code "117") (name "VDDDAC33") (class "Default")
      (node (ref "C46") (pin "2") (pinfunction "2_2") (pintype "passive"))
      (node (ref "C47") (pin "2") (pinfunction "2_2") (pintype "passive"))
      (node (ref "C48") (pin "2") (pinfunction "2_2") (pintype "passive"))
      (node (ref "C49") (pin "2") (pinfunction "2_2") (pintype "passive"))
      (node (ref "FB9") (pin "2") (pinfunction "2_2") (pintype "passive"))
      (node (ref "U1") (pin "D10") (pinfunction "VDDDAC33_D10") (pintype "passive"))
      (node (ref "U1") (pin "E10") (pinfunction "VDDDAC33_E10") (pintype "passive"))
      (node (ref "U1") (pin "H10") (pinfunction "VDDDAC33_H10") (pintype "passive"))
      (node (ref "U1") (pin "J10") (pinfunction "VDDDAC33_J10") (pintype "passive"))
    )
    (net (code "118") (name "VDDDIG09") (class "Default")
      (node (ref "U1") (pin "D3") (pinfunction "VDDDIG09_D3") (pintype "passive"))
      (node (ref "U1") (pin "D4") (pinfunction "VDDDIG09_D4") (pintype "passive"))
      (node (ref "U1") (pin "D5") (pinfunction "VDDDIG09_D5") (pintype "passive"))
      (node (ref "U1") (pin "E4") (pinfunction "VDDDIG09_E4") (pintype "passive"))
      (node (ref "U1") (pin "F4") (pinfunction "VDDDIG09_F4") (pintype "passive"))
      (node (ref "U1") (pin "G4") (pinfunction "VDDDIG09_G4") (pintype "passive"))
      (node (ref "U1") (pin "H4") (pinfunction "VDDDIG09_H4") (pintype "passive"))
      (node (ref "U1") (pin "J4") (pinfunction "VDDDIG09_J4") (pintype "passive"))
      (node (ref "U1") (pin "J5") (pinfunction "VDDDIG09_J5") (pintype "passive"))
      (node (ref "U1") (pin "J6") (pinfunction "VDDDIG09_J6") (pintype "passive"))
      (node (ref "U1") (pin "J7") (pinfunction "VDDDIG09_J7") (pintype "passive"))
    )
    (net (code "119") (name "VDDIO18") (class "Default")
      (node (ref "U1") (pin "K6") (pinfunction "VDDIO18_K6") (pintype "passive"))
      (node (ref "U1") (pin "K7") (pinfunction "VDDIO18_K7") (pintype "passive"))
    )
    (net (code "120") (name "VDDR18") (class "Default")
      (node (ref "U1") (pin "F2") (pinfunction "VDDR18_F2") (pintype "passive"))
      (node (ref "U1") (pin "G2") (pinfunction "VDDR18_G2") (pintype "passive"))
    )
    (net (code "121") (name "VDDS18") (class "Default")
      (node (ref "U1") (pin "C6") (pinfunction "VDDS18_C6") (pintype "passive"))
      (node (ref "U1") (pin "C7") (pinfunction "VDDS18_C7") (pintype "passive"))
      (node (ref "U1") (pin "D6") (pinfunction "VQPS18_D6") (pintype "passive"))
      (node (ref "U1") (pin "D7") (pinfunction "VQPS18_D7") (pintype "passive"))
    )
    (net (code "122") (name "VDDT09") (class "Default")
      (node (ref "U1") (pin "F3") (pinfunction "VDDT09_F3") (pintype "passive"))
      (node (ref "U1") (pin "G3") (pinfunction "VDDT09_G3") (pintype "passive"))
    )
    (net (code "123") (name "VPLL19") (class "Default")
      (node (ref "C27") (pin "2") (pinfunction "2_2") (pintype "passive"))
      (node (ref "C28") (pin "2") (pinfunction "2_2") (pintype "passive"))
      (node (ref "FB2") (pin "2") (pinfunction "2_2") (pintype "passive"))
      (node (ref "U2") (pin "J4") (pinfunction "VPLL19_J4") (pintype "passive"))
      (node (ref "U2") (pin "J5") (pinfunction "VPLL19_J5") (pintype "passive"))
    )
    (net (code "124") (name "VREFO") (class "Default")
      (node (ref "C35") (pin "2") (pinfunction "2_2") (pintype "passive"))
      (node (ref "C36") (pin "2") (pinfunction "2_2") (pintype "passive"))
      (node (ref "FB4") (pin "2") (pinfunction "2_2") (pintype "passive"))
      (node (ref "U2") (pin "K6") (pinfunction "VREFO_K6") (pintype "passive"))
    )
    (net (code "125") (name "VTRIG") (class "Default")
      (node (ref "C37") (pin "2") (pinfunction "2_2") (pintype "passive"))
      (node (ref "C38") (pin "2") (pinfunction "2_2") (pintype "passive"))
      (node (ref "FB5") (pin "2") (pinfunction "2_2") (pintype "passive"))
      (node (ref "U2") (pin "J8") (pinfunction "VTRIG_J8") (pintype "passive"))
      (node (ref "U2") (pin "K8") (pinfunction "VTRIG_K8") (pintype "passive"))
    )
    (net (code "126") (name "unconnected-(J1-Pad01)") (class "Default")
      (node (ref "J1") (pin "01") (pinfunction "01_01") (pintype "passive"))
    )
    (net (code "127") (name "unconnected-(J1-Pad03)") (class "Default")
      (node (ref "J1") (pin "03") (pinfunction "03_03") (pintype "passive"))
    )
    (net (code "128") (name "unconnected-(J1-Pad04)") (class "Default")
      (node (ref "J1") (pin "04") (pinfunction "04_04") (pintype "passive"))
    )
    (net (code "129") (name "unconnected-(J1-Pad16)") (class "Default")
      (node (ref "J1") (pin "16") (pinfunction "16_16") (pintype "passive"))
    )
    (net (code "130") (name "unconnected-(J1-Pad17)") (class "Default")
      (node (ref "J1") (pin "17") (pinfunction "17_17") (pintype "passive"))
    )
    (net (code "131") (name "unconnected-(J1-Pad19)") (class "Default")
      (node (ref "J1") (pin "19") (pinfunction "19_19") (pintype "passive"))
    )
    (net (code "132") (name "unconnected-(J1-Pad21)") (class "Default")
      (node (ref "J1") (pin "21") (pinfunction "21_21") (pintype "passive"))
    )
    (net (code "133") (name "unconnected-(J1-Pad23)") (class "Default")
      (node (ref "J1") (pin "23") (pinfunction "23_23") (pintype "passive"))
    )
    (net (code "134") (name "unconnected-(J1-Pad37)") (class "Default")
      (node (ref "J1") (pin "37") (pinfunction "37_37") (pintype "passive+no_connect"))
    )
    (net (code "135") (name "unconnected-(J1-Pad38)") (class "Default")
      (node (ref "J1") (pin "38") (pinfunction "38_38") (pintype "passive+no_connect"))
    )
    (net (code "136") (name "unconnected-(J1-Pad39)") (class "Default")
      (node (ref "J1") (pin "39") (pinfunction "39_39") (pintype "passive"))
    )
    (net (code "137") (name "unconnected-(J2-Pad01)") (class "Default")
      (node (ref "J2") (pin "01") (pinfunction "01_01") (pintype "passive"))
    )
    (net (code "138") (name "unconnected-(J2-Pad03)") (class "Default")
      (node (ref "J2") (pin "03") (pinfunction "03_03") (pintype "passive"))
    )
    (net (code "139") (name "unconnected-(J2-Pad04)") (class "Default")
      (node (ref "J2") (pin "04") (pinfunction "04_04") (pintype "passive"))
    )
    (net (code "140") (name "unconnected-(J2-Pad17)") (class "Default")
      (node (ref "J2") (pin "17") (pinfunction "17_17") (pintype "bidirectional"))
    )
    (net (code "141") (name "unconnected-(J2-Pad19)") (class "Default")
      (node (ref "J2") (pin "19") (pinfunction "19_19") (pintype "bidirectional"))
    )
    (net (code "142") (name "unconnected-(J2-Pad21)") (class "Default")
      (node (ref "J2") (pin "21") (pinfunction "21_21") (pintype "bidirectional"))
    )
    (net (code "143") (name "unconnected-(J2-Pad22)") (class "Default")
      (node (ref "J2") (pin "22") (pinfunction "22_22") (pintype "bidirectional"))
    )
    (net (code "144") (name "unconnected-(J2-Pad23)") (class "Default")
      (node (ref "J2") (pin "23") (pinfunction "23_23") (pintype "bidirectional"))
    )
    (net (code "145") (name "unconnected-(J2-Pad24)") (class "Default")
      (node (ref "J2") (pin "24") (pinfunction "24_24") (pintype "bidirectional"))
    )
    (net (code "146") (name "unconnected-(J2-Pad37)") (class "Default")
      (node (ref "J2") (pin "37") (pinfunction "37_37") (pintype "passive+no_connect"))
    )
    (net (code "147") (name "unconnected-(J2-Pad38)") (class "Default")
      (node (ref "J2") (pin "38") (pinfunction "38_38") (pintype "passive+no_connect"))
    )
    (net (code "148") (name "unconnected-(J2-Pad39)") (class "Default")
      (node (ref "J2") (pin "39") (pinfunction "39_39") (pintype "passive"))
    )
    (net (code "149") (name "unconnected-(J6-Pad5)") (class "Default")
      (node (ref "J6") (pin "5") (pinfunction "5_5") (pintype "output"))
    )
    (net (code "150") (name "unconnected-(U1A-NC-PadM6)") (class "Default")
      (node (ref "U1") (pin "M6") (pinfunction "NC_M6") (pintype "passive+no_connect"))
    )
    (net (code "151") (name "unconnected-(U1A-NC-PadM7)") (class "Default")
      (node (ref "U1") (pin "M7") (pinfunction "NC_M7") (pintype "passive+no_connect"))
    )
    (net (code "152") (name "unconnected-(U1A-TESTMODE-PadK3)") (class "Default")
      (node (ref "U1") (pin "K3") (pinfunction "TESTMODE_K3") (pintype "output+no_connect"))
    )
    (net (code "153") (name "unconnected-(U1B-DACCLKN-PadA9)") (class "Default")
      (node (ref "U1") (pin "A9") (pinfunction "DACCLKN_A9") (pintype "input"))
    )
    (net (code "154") (name "unconnected-(U1B-DACCLKP-PadA10)") (class "Default")
      (node (ref "U1") (pin "A10") (pinfunction "DACCLKP_A10") (pintype "input"))
    )
    (net (code "155") (name "unconnected-(U1C-AMUX0-PadH3)") (class "Default")
      (node (ref "U1") (pin "H3") (pinfunction "AMUX0_H3") (pintype "bidirectional"))
    )
    (net (code "156") (name "unconnected-(U1C-AMUX1-PadE3)") (class "Default")
      (node (ref "U1") (pin "E3") (pinfunction "AMUX1_E3") (pintype "bidirectional"))
    )
    (net (code "157") (name "unconnected-(U1C-ATEST-PadK9)") (class "Default")
      (node (ref "U1") (pin "K9") (pinfunction "ATEST_K9") (pintype "bidirectional"))
    )
    (net (code "158") (name "unconnected-(U1C-EXTIO-PadF10)") (class "Default")
      (node (ref "U1") (pin "F10") (pinfunction "EXTIO_F10") (pintype "bidirectional"))
    )
    (net (code "159") (name "unconnected-(U1C-IFORCE-PadC5)") (class "Default")
      (node (ref "U1") (pin "C5") (pinfunction "IFORCE_C5") (pintype "bidirectional"))
    )
    (net (code "160") (name "unconnected-(U1C-IOUTBN-PadD12)") (class "Default")
      (node (ref "U1") (pin "D12") (pinfunction "IOUTBN_D12") (pintype "output+no_connect"))
    )
    (net (code "161") (name "unconnected-(U1C-IOUTBP-PadE12)") (class "Default")
      (node (ref "U1") (pin "E12") (pinfunction "IOUTBP_E12") (pintype "output+no_connect"))
    )
    (net (code "162") (name "unconnected-(U1C-IOUTDN-PadK12)") (class "Default")
      (node (ref "U1") (pin "K12") (pinfunction "IOUTDN_K12") (pintype "output+no_connect"))
    )
    (net (code "163") (name "unconnected-(U1C-IOUTDP-PadL12)") (class "Default")
      (node (ref "U1") (pin "L12") (pinfunction "IOUTDP_L12") (pintype "output+no_connect"))
    )
    (net (code "164") (name "unconnected-(U1C-LPF-PadC9)") (class "Default")
      (node (ref "U1") (pin "C9") (pinfunction "LPF_C9") (pintype "bidirectional"))
    )
    (net (code "165") (name "unconnected-(U1C-RBIAS-PadG10)") (class "Default")
      (node (ref "U1") (pin "G10") (pinfunction "RBIAS_G10") (pintype "output"))
    )
    (net (code "166") (name "unconnected-(U1C-VSENSE-PadC4)") (class "Default")
      (node (ref "U1") (pin "C4") (pinfunction "VSENSE_C4") (pintype "bidirectional"))
    )
    (net (code "167") (name "unconnected-(U2B-ADCCLKN-PadG1)") (class "Default")
      (node (ref "U2") (pin "G1") (pinfunction "ADCCLKN_G1") (pintype "input"))
    )
    (net (code "168") (name "unconnected-(U2B-ADCCLKP-PadF1)") (class "Default")
      (node (ref "U2") (pin "F1") (pinfunction "ADCCLKP_F1") (pintype "input"))
    )
    (net (code "169") (name "unconnected-(U2B-SE_CLK-PadF2)") (class "Default")
      (node (ref "U2") (pin "F2") (pinfunction "SE_CLK_F2") (pintype "input+no_connect"))
    )
    (net (code "170") (name "unconnected-(U2C-CLKCFG0-PadC7)") (class "Default")
      (node (ref "U2") (pin "C7") (pinfunction "CLKCFG0_C7") (pintype "input"))
    )
    (net (code "171") (name "unconnected-(U2C-CLKCFG1-PadD7)") (class "Default")
      (node (ref "U2") (pin "D7") (pinfunction "CLKCFG1_D7") (pintype "input"))
    )
    (net (code "172") (name "unconnected-(U2C-ORA-PadC9)") (class "Default")
      (node (ref "U2") (pin "C9") (pinfunction "ORA_C9") (pintype "output"))
    )
    (net (code "173") (name "unconnected-(U2C-ORB-PadD9)") (class "Default")
      (node (ref "U2") (pin "D9") (pinfunction "ORB_D9") (pintype "output"))
    )
    (net (code "174") (name "unconnected-(U2C-ORC-PadE9)") (class "Default")
      (node (ref "U2") (pin "E9") (pinfunction "ORC_E9") (pintype "output"))
    )
    (net (code "175") (name "unconnected-(U2C-ORD-PadF9)") (class "Default")
      (node (ref "U2") (pin "F9") (pinfunction "ORD_F9") (pintype "output"))
    )
    (net (code "176") (name "unconnected-(U2C-PLLEN-PadD8)") (class "Default")
      (node (ref "U2") (pin "D8") (pinfunction "PLLEN_D8") (pintype "input"))
    )
    (net (code "177") (name "unconnected-(U2C-PLLREFON-PadK7)") (class "Default")
      (node (ref "U2") (pin "K7") (pinfunction "PLLREFON_K7") (pintype "output"))
    )
    (net (code "178") (name "unconnected-(U2C-PLLREFOP-PadJ7)") (class "Default")
      (node (ref "U2") (pin "J7") (pinfunction "PLLREFOP_J7") (pintype "output"))
    )
    (net (code "179") (name "unconnected-(U2C-PLLREF_SE-PadC8)") (class "Default")
      (node (ref "U2") (pin "C8") (pinfunction "PLLREF_SE_C8") (pintype "input"))
    )
    (net (code "180") (name "unconnected-(U2E-BG-PadC3)") (class "Default")
      (node (ref "U2") (pin "C3") (pinfunction "BG_C3") (pintype "output"))
    )
    (net (code "181") (name "unconnected-(U2E-CALSTAT-PadB9)") (class "Default")
      (node (ref "U2") (pin "B9") (pinfunction "CALSTAT_B9") (pintype "output"))
    )
    (net (code "182") (name "unconnected-(U2E-CALTRIG-PadA9)") (class "Default")
      (node (ref "U2") (pin "A9") (pinfunction "CALTRIG_A9") (pintype "input"))
    )
    (net (code "183") (name "unconnected-(U2E-INCN-PadM6)") (class "Default")
      (node (ref "U2") (pin "M6") (pinfunction "INCN_M6") (pintype "input+no_connect"))
    )
    (net (code "184") (name "unconnected-(U2E-INCP-PadM7)") (class "Default")
      (node (ref "U2") (pin "M7") (pinfunction "INCP_M7") (pintype "input+no_connect"))
    )
    (net (code "185") (name "unconnected-(U2E-INDN-PadM3)") (class "Default")
      (node (ref "U2") (pin "M3") (pinfunction "INDN_M3") (pintype "input+no_connect"))
    )
    (net (code "186") (name "unconnected-(U2E-INDP-PadM2)") (class "Default")
      (node (ref "U2") (pin "M2") (pinfunction "INDP_M2") (pintype "input+no_connect"))
    )
    (net (code "187") (name "unconnected-(U2E-PD-PadM9)") (class "Default")
      (node (ref "U2") (pin "M9") (pinfunction "PD_M9") (pintype "input"))
    )
    (net (code "188") (name "unconnected-(U2E-TDIODEN-PadK4)") (class "Default")
      (node (ref "U2") (pin "K4") (pinfunction "TDIODEN_K4") (pintype "input"))
    )
    (net (code "189") (name "unconnected-(U2E-TDIODEP-PadK3)") (class "Default")
      (node (ref "U2") (pin "K3") (pinfunction "TDIODEP_K3") (pintype "input"))
    )
    (net (code "190") (name "unconnected-(U2E-TMSTP_N-PadD1)") (class "Default")
      (node (ref "U2") (pin "D1") (pinfunction "TMSTP_N_D1") (pintype "input"))
    )
    (net (code "191") (name "unconnected-(U2E-TMSTP_P-PadC1)") (class "Default")
      (node (ref "U2") (pin "C1") (pinfunction "TMSTP_P_C1") (pintype "input"))
    )
    (net (code "192") (name "unconnected-(U2E-TRIGOUTN-PadK9)") (class "Default")
      (node (ref "U2") (pin "K9") (pinfunction "TRIGOUTN_K9") (pintype "output"))
    )
    (net (code "193") (name "unconnected-(U2E-TRIGOUTP-PadJ9)") (class "Default")
      (node (ref "U2") (pin "J9") (pinfunction "TRIGOUTP_J9") (pintype "output"))
    )
    (net (code "194") (name "unconnected-(U3-AVCC-Pad48)") (class "Default")
      (node (ref "U3") (pin "48") (pinfunction "AVCC_48") (pintype "passive"))
    )
    (net (code "195") (name "unconnected-(U3-AVSS-Pad41)") (class "Default")
      (node (ref "U3") (pin "41") (pinfunction "AVSS_41") (pintype "passive"))
    )
    (net (code "196") (name "unconnected-(U3-AVSS-Pad44)") (class "Default")
      (node (ref "U3") (pin "44") (pinfunction "AVSS_44") (pintype "passive"))
    )
    (net (code "197") (name "unconnected-(U3-AVSS-Pad47)") (class "Default")
      (node (ref "U3") (pin "47") (pinfunction "AVSS_47") (pintype "passive"))
    )
    (net (code "198") (name "unconnected-(U3-DVCC-Pad37)") (class "Default")
      (node (ref "U3") (pin "37") (pinfunction "DVCC_37") (pintype "passive"))
    )
    (net (code "199") (name "unconnected-(U3-DVSS-Pad36)") (class "Default")
      (node (ref "U3") (pin "36") (pinfunction "DVSS_36") (pintype "passive"))
    )
    (net (code "200") (name "unconnected-(U3-P1.0{slash}TA0.1{slash}DMAE0{slash}RTCCLK{slash}A0{slash}C0{slash}VREF-{slash}VeREF--Pad1)") (class "Default")
      (node (ref "U3") (pin "1") (pinfunction "P1.0/TA0.1/DMAE0/RTCCLK/A0/C0/VREF-/VeREF-_1") (pintype "passive"))
    )
    (net (code "201") (name "unconnected-(U3-P1.1{slash}TA0.2{slash}TA1CLK{slash}COUT{slash}A1{slash}C1{slash}VREF+{slash}VeREF+-Pad2)") (class "Default")
      (node (ref "U3") (pin "2") (pinfunction "P1.1/TA0.2/TA1CLK/COUT/A1/C1/VREF+/VeREF+_2") (pintype "passive"))
    )
    (net (code "202") (name "unconnected-(U3-P1.2{slash}TA1.1{slash}TA0CLK{slash}COUT{slash}A2{slash}C2-Pad3)") (class "Default")
      (node (ref "U3") (pin "3") (pinfunction "P1.2/TA1.1/TA0CLK/COUT/A2/C2_3") (pintype "passive"))
    )
    (net (code "203") (name "unconnected-(U3-P1.3{slash}TA1.2{slash}UCB0STE{slash}A3{slash}C3-Pad9)") (class "Default")
      (node (ref "U3") (pin "9") (pinfunction "P1.3/TA1.2/UCB0STE/A3/C3_9") (pintype "passive"))
    )
    (net (code "204") (name "unconnected-(U3-P1.4{slash}TB0.1{slash}UCA0STE{slash}A4{slash}C4-Pad10)") (class "Default")
      (node (ref "U3") (pin "10") (pinfunction "P1.4/TB0.1/UCA0STE/A4/C4_10") (pintype "passive"))
    )
    (net (code "205") (name "unconnected-(U3-P1.5{slash}TB0.2{slash}UCA0CLK{slash}A5{slash}C5-Pad11)") (class "Default")
      (node (ref "U3") (pin "11") (pinfunction "P1.5/TB0.2/UCA0CLK/A5/C5_11") (pintype "passive"))
    )
    (net (code "206") (name "unconnected-(U3-P1.6{slash}TB0.3{slash}UCB0SIMO{slash}UCB0SDA{slash}TA0.0-Pad31)") (class "Default")
      (node (ref "U3") (pin "31") (pinfunction "P1.6/TB0.3/UCB0SIMO/UCB0SDA/TA0.0_31") (pintype "passive"))
    )
    (net (code "207") (name "unconnected-(U3-P1.7{slash}TB0.4{slash}UCB0SOMI{slash}UCB0SCL{slash}TA1.0-Pad32)") (class "Default")
      (node (ref "U3") (pin "32") (pinfunction "P1.7/TB0.4/UCB0SOMI/UCB0SCL/TA1.0_32") (pintype "passive"))
    )
    (net (code "208") (name "unconnected-(U3-P2.0{slash}TB0.6{slash}UCA0TXD{slash}UCA0SIMO{slash}TB0CLK{slash}ACLK-Pad24)") (class "Default")
      (node (ref "U3") (pin "24") (pinfunction "P2.0/TB0.6/UCA0TXD/UCA0SIMO/TB0CLK/ACLK_24") (pintype "passive"))
    )
    (net (code "209") (name "unconnected-(U3-P2.1{slash}TB0.0{slash}UCA0RXD{slash}UCA0SOMI{slash}TB0.0-Pad25)") (class "Default")
      (node (ref "U3") (pin "25") (pinfunction "P2.1/TB0.0/UCA0RXD/UCA0SOMI/TB0.0_25") (pintype "passive"))
    )
    (net (code "210") (name "unconnected-(U3-P2.2{slash}TB0.2{slash}UCB0CLK-Pad26)") (class "Default")
      (node (ref "U3") (pin "26") (pinfunction "P2.2/TB0.2/UCB0CLK_26") (pintype "passive"))
    )
    (net (code "211") (name "unconnected-(U3-P2.3{slash}TA0.0{slash}UCA1STE{slash}A6{slash}C10-Pad39)") (class "Default")
      (node (ref "U3") (pin "39") (pinfunction "P2.3/TA0.0/UCA1STE/A6/C10_39") (pintype "passive"))
    )
    (net (code "212") (name "unconnected-(U3-P2.4{slash}TA1.0{slash}UCA1CLK{slash}A7{slash}C11-Pad40)") (class "Default")
      (node (ref "U3") (pin "40") (pinfunction "P2.4/TA1.0/UCA1CLK/A7/C11_40") (pintype "passive"))
    )
    (net (code "213") (name "unconnected-(U3-P2.5{slash}TB0.0{slash}UCA1TXD{slash}UCA1SIMO-Pad20)") (class "Default")
      (node (ref "U3") (pin "20") (pinfunction "P2.5/TB0.0/UCA1TXD/UCA1SIMO_20") (pintype "passive"))
    )
    (net (code "214") (name "unconnected-(U3-P2.6{slash}TB0.1{slash}UCA1RXD{slash}UCA1SOMI-Pad21)") (class "Default")
      (node (ref "U3") (pin "21") (pinfunction "P2.6/TB0.1/UCA1RXD/UCA1SOMI_21") (pintype "passive"))
    )
    (net (code "215") (name "unconnected-(U3-P2.7-Pad38)") (class "Default")
      (node (ref "U3") (pin "38") (pinfunction "P2.7_38") (pintype "passive"))
    )
    (net (code "216") (name "unconnected-(U3-P3.0{slash}A12{slash}C12-Pad4)") (class "Default")
      (node (ref "U3") (pin "4") (pinfunction "P3.0/A12/C12_4") (pintype "passive"))
    )
    (net (code "217") (name "unconnected-(U3-P3.1{slash}A13{slash}C13-Pad5)") (class "Default")
      (node (ref "U3") (pin "5") (pinfunction "P3.1/A13/C13_5") (pintype "passive"))
    )
    (net (code "218") (name "unconnected-(U3-P3.2{slash}A14{slash}C14-Pad6)") (class "Default")
      (node (ref "U3") (pin "6") (pinfunction "P3.2/A14/C14_6") (pintype "passive"))
    )
    (net (code "219") (name "unconnected-(U3-P3.3{slash}A15{slash}C15-Pad7)") (class "Default")
      (node (ref "U3") (pin "7") (pinfunction "P3.3/A15/C15_7") (pintype "passive"))
    )
    (net (code "220") (name "unconnected-(U3-P3.4{slash}TB0.3{slash}SMCLK-Pad27)") (class "Default")
      (node (ref "U3") (pin "27") (pinfunction "P3.4/TB0.3/SMCLK_27") (pintype "passive"))
    )
    (net (code "221") (name "unconnected-(U3-P3.5{slash}TB0.4{slash}COUT-Pad28)") (class "Default")
      (node (ref "U3") (pin "28") (pinfunction "P3.5/TB0.4/COUT_28") (pintype "passive"))
    )
    (net (code "222") (name "unconnected-(U3-P3.6{slash}TB0.5-Pad29)") (class "Default")
      (node (ref "U3") (pin "29") (pinfunction "P3.6/TB0.5_29") (pintype "passive"))
    )
    (net (code "223") (name "unconnected-(U3-P3.7{slash}TB0.6-Pad30)") (class "Default")
      (node (ref "U3") (pin "30") (pinfunction "P3.7/TB0.6_30") (pintype "passive"))
    )
    (net (code "224") (name "unconnected-(U3-P4.0{slash}A8-Pad16)") (class "Default")
      (node (ref "U3") (pin "16") (pinfunction "P4.0/A8_16") (pintype "passive"))
    )
    (net (code "225") (name "unconnected-(U3-P4.1{slash}A9-Pad17)") (class "Default")
      (node (ref "U3") (pin "17") (pinfunction "P4.1/A9_17") (pintype "passive"))
    )
    (net (code "226") (name "unconnected-(U3-P4.2{slash}A10-Pad18)") (class "Default")
      (node (ref "U3") (pin "18") (pinfunction "P4.2/A10_18") (pintype "passive"))
    )
    (net (code "227") (name "unconnected-(U3-P4.3{slash}A11-Pad19)") (class "Default")
      (node (ref "U3") (pin "19") (pinfunction "P4.3/A11_19") (pintype "passive"))
    )
    (net (code "228") (name "unconnected-(U3-P4.4{slash}TB0.5-Pad33)") (class "Default")
      (node (ref "U3") (pin "33") (pinfunction "P4.4/TB0.5_33") (pintype "passive"))
    )
    (net (code "229") (name "unconnected-(U3-P4.5-Pad34)") (class "Default")
      (node (ref "U3") (pin "34") (pinfunction "P4.5_34") (pintype "passive"))
    )
    (net (code "230") (name "unconnected-(U3-P4.6-Pad35)") (class "Default")
      (node (ref "U3") (pin "35") (pinfunction "P4.6_35") (pintype "passive"))
    )
    (net (code "231") (name "unconnected-(U3-P4.7-Pad8)") (class "Default")
      (node (ref "U3") (pin "8") (pinfunction "P4.7_8") (pintype "passive"))
    )
    (net (code "232") (name "unconnected-(U3-PJ.4{slash}LFXIN-Pad45)") (class "Default")
      (node (ref "U3") (pin "45") (pinfunction "PJ.4/LFXIN_45") (pintype "passive"))
    )
    (net (code "233") (name "unconnected-(U3-PJ.5{slash}LFXOUT-Pad46)") (class "Default")
      (node (ref "U3") (pin "46") (pinfunction "PJ.5/LFXOUT_46") (pintype "passive"))
    )
    (net (code "234") (name "unconnected-(U3-PJ.6{slash}HFXIN-Pad42)") (class "Default")
      (node (ref "U3") (pin "42") (pinfunction "PJ.6/HFXIN_42") (pintype "passive"))
    )
    (net (code "235") (name "unconnected-(U3-PJ.7{slash}HFXOUT-Pad43)") (class "Default")
      (node (ref "U3") (pin "43") (pinfunction "PJ.7/HFXOUT_43") (pintype "passive"))
    )
    (net (code "236") (name "unconnected-(U3-TEST{slash}SBWTCK-Pad22)") (class "Default")
      (node (ref "U3") (pin "22") (pinfunction "TEST/SBWTCK_22") (pintype "passive"))
    )
    (net (code "237") (name "unconnected-(U3-VSS_PAD-Pad49)") (class "Default")
      (node (ref "U3") (pin "49") (pinfunction "VSS_PAD_49") (pintype "passive"))
    )
    (net (code "238") (name "unconnected-(U3-~{RST}{slash}NMI{slash}SBWTDIO-Pad23)") (class "Default")
      (node (ref "U3") (pin "23") (pinfunction "~{RST}/NMI/SBWTDIO_23") (pintype "passive"))
    )
  )
)
